# HW_RPI_10in_Rack.net
KiCad netlist of a schematic drawn in EAGLE
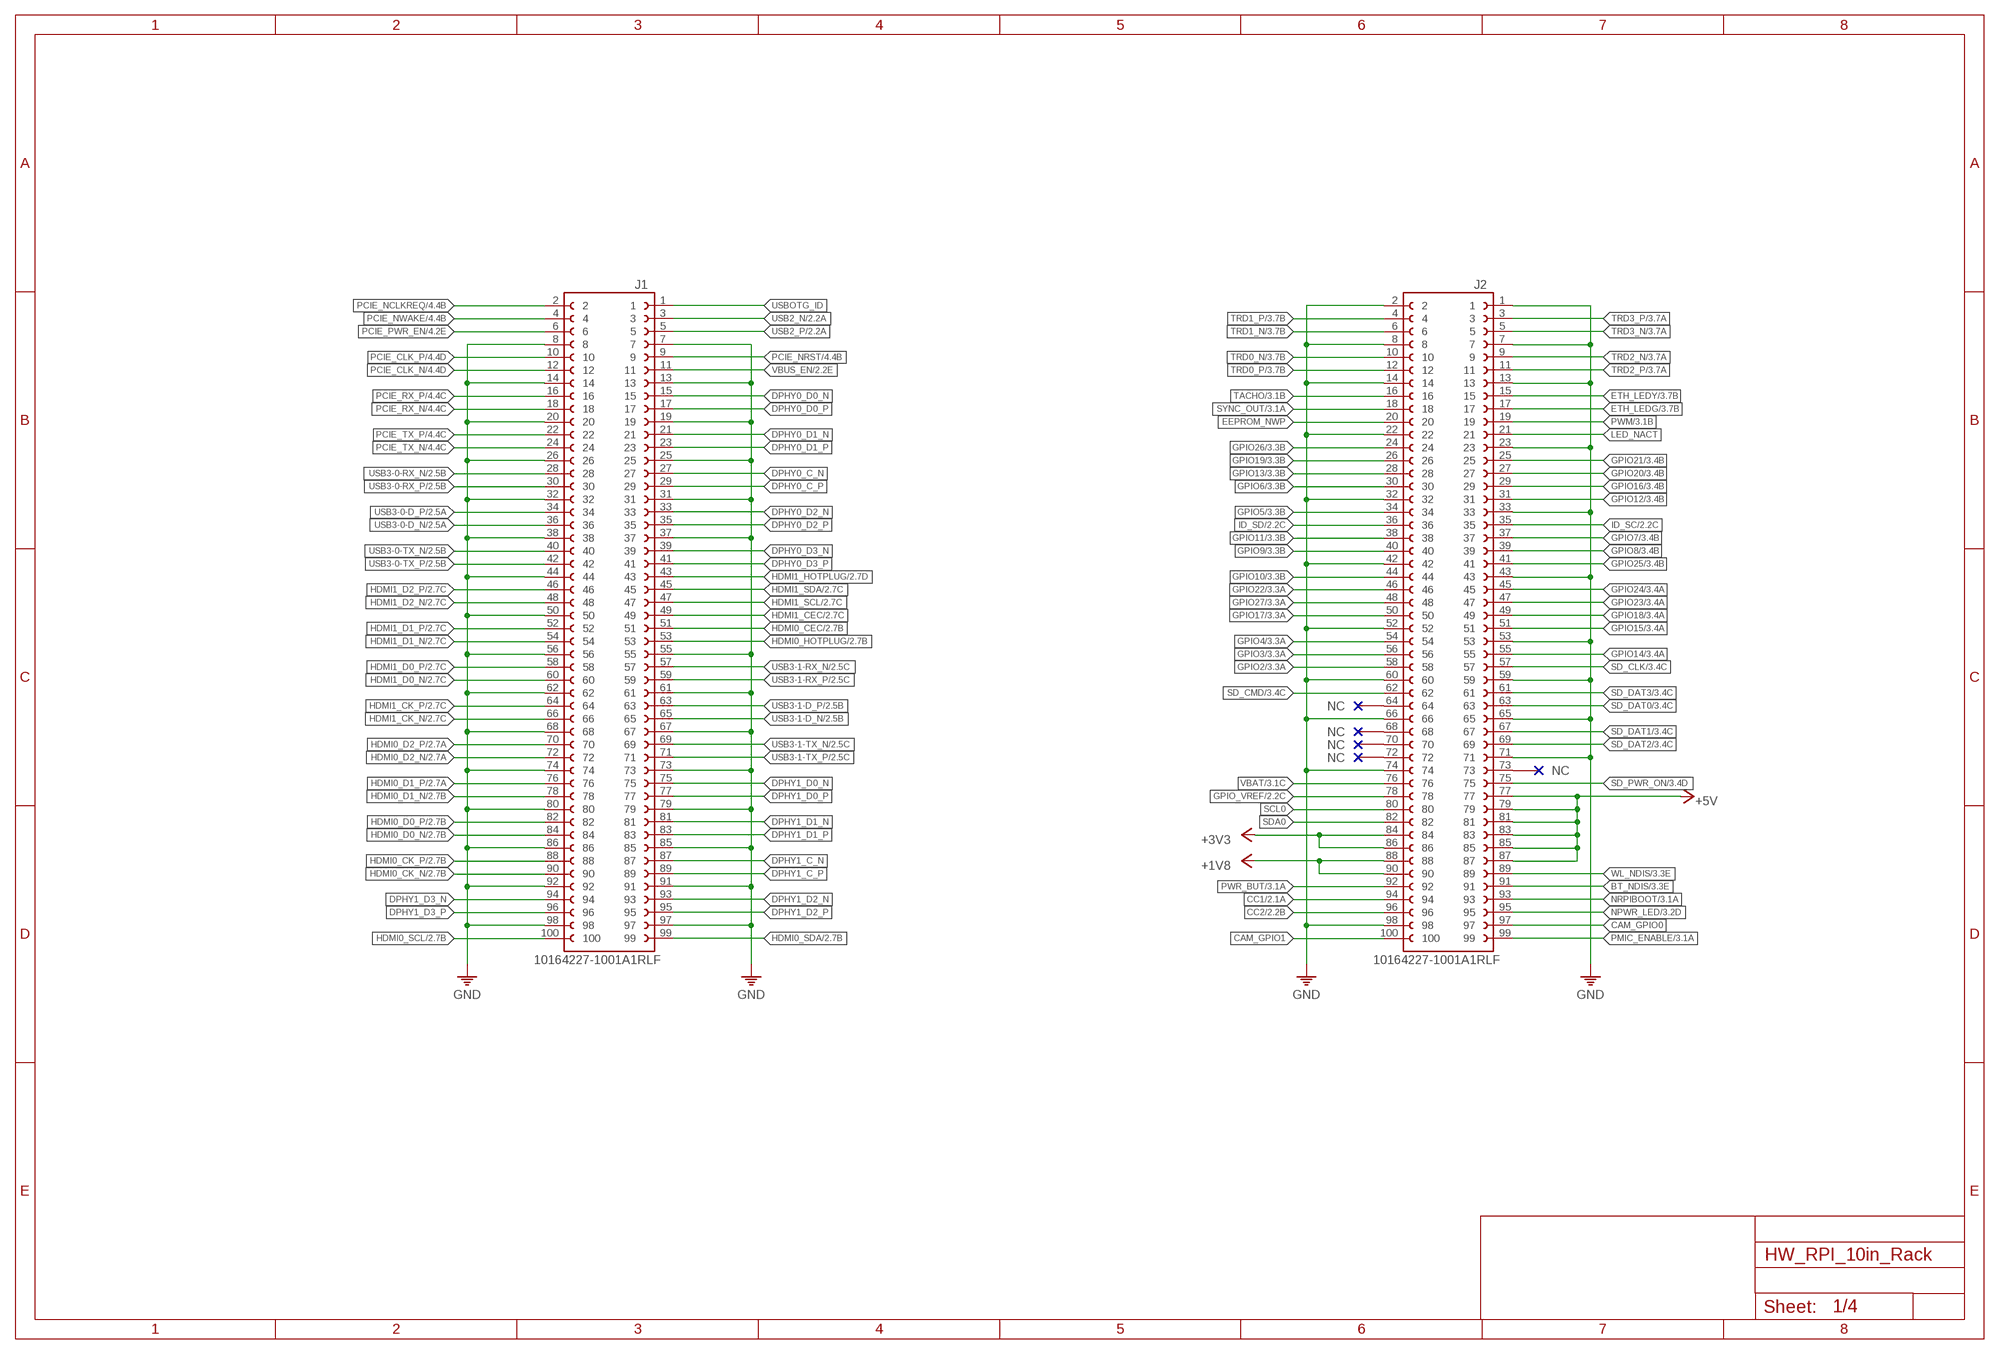
[diagram p0: schematic, sheet 1]
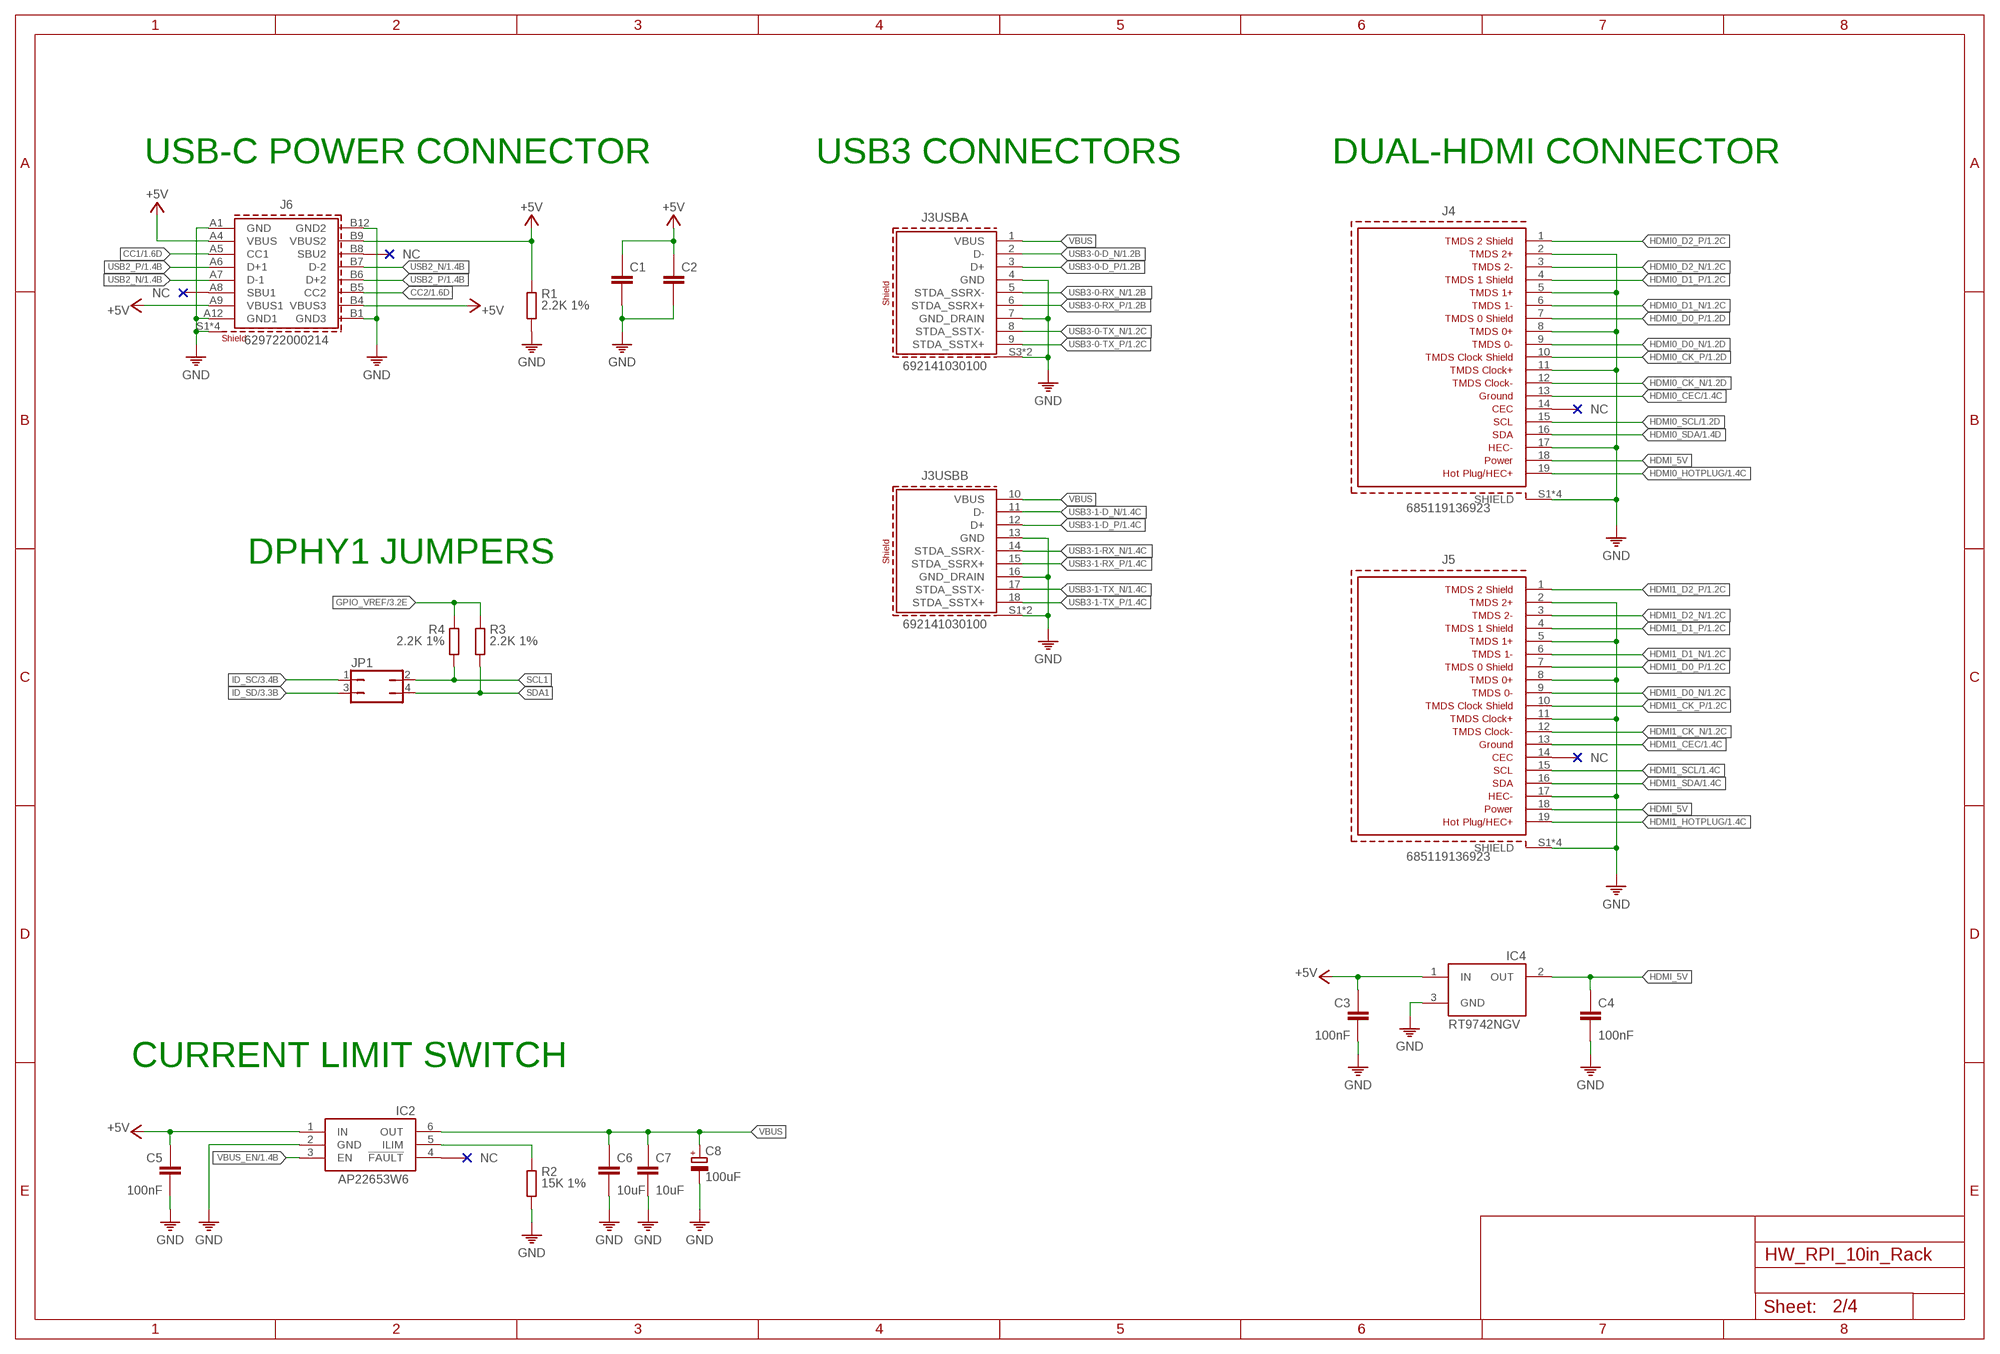
[diagram p1: schematic, sheet 2]
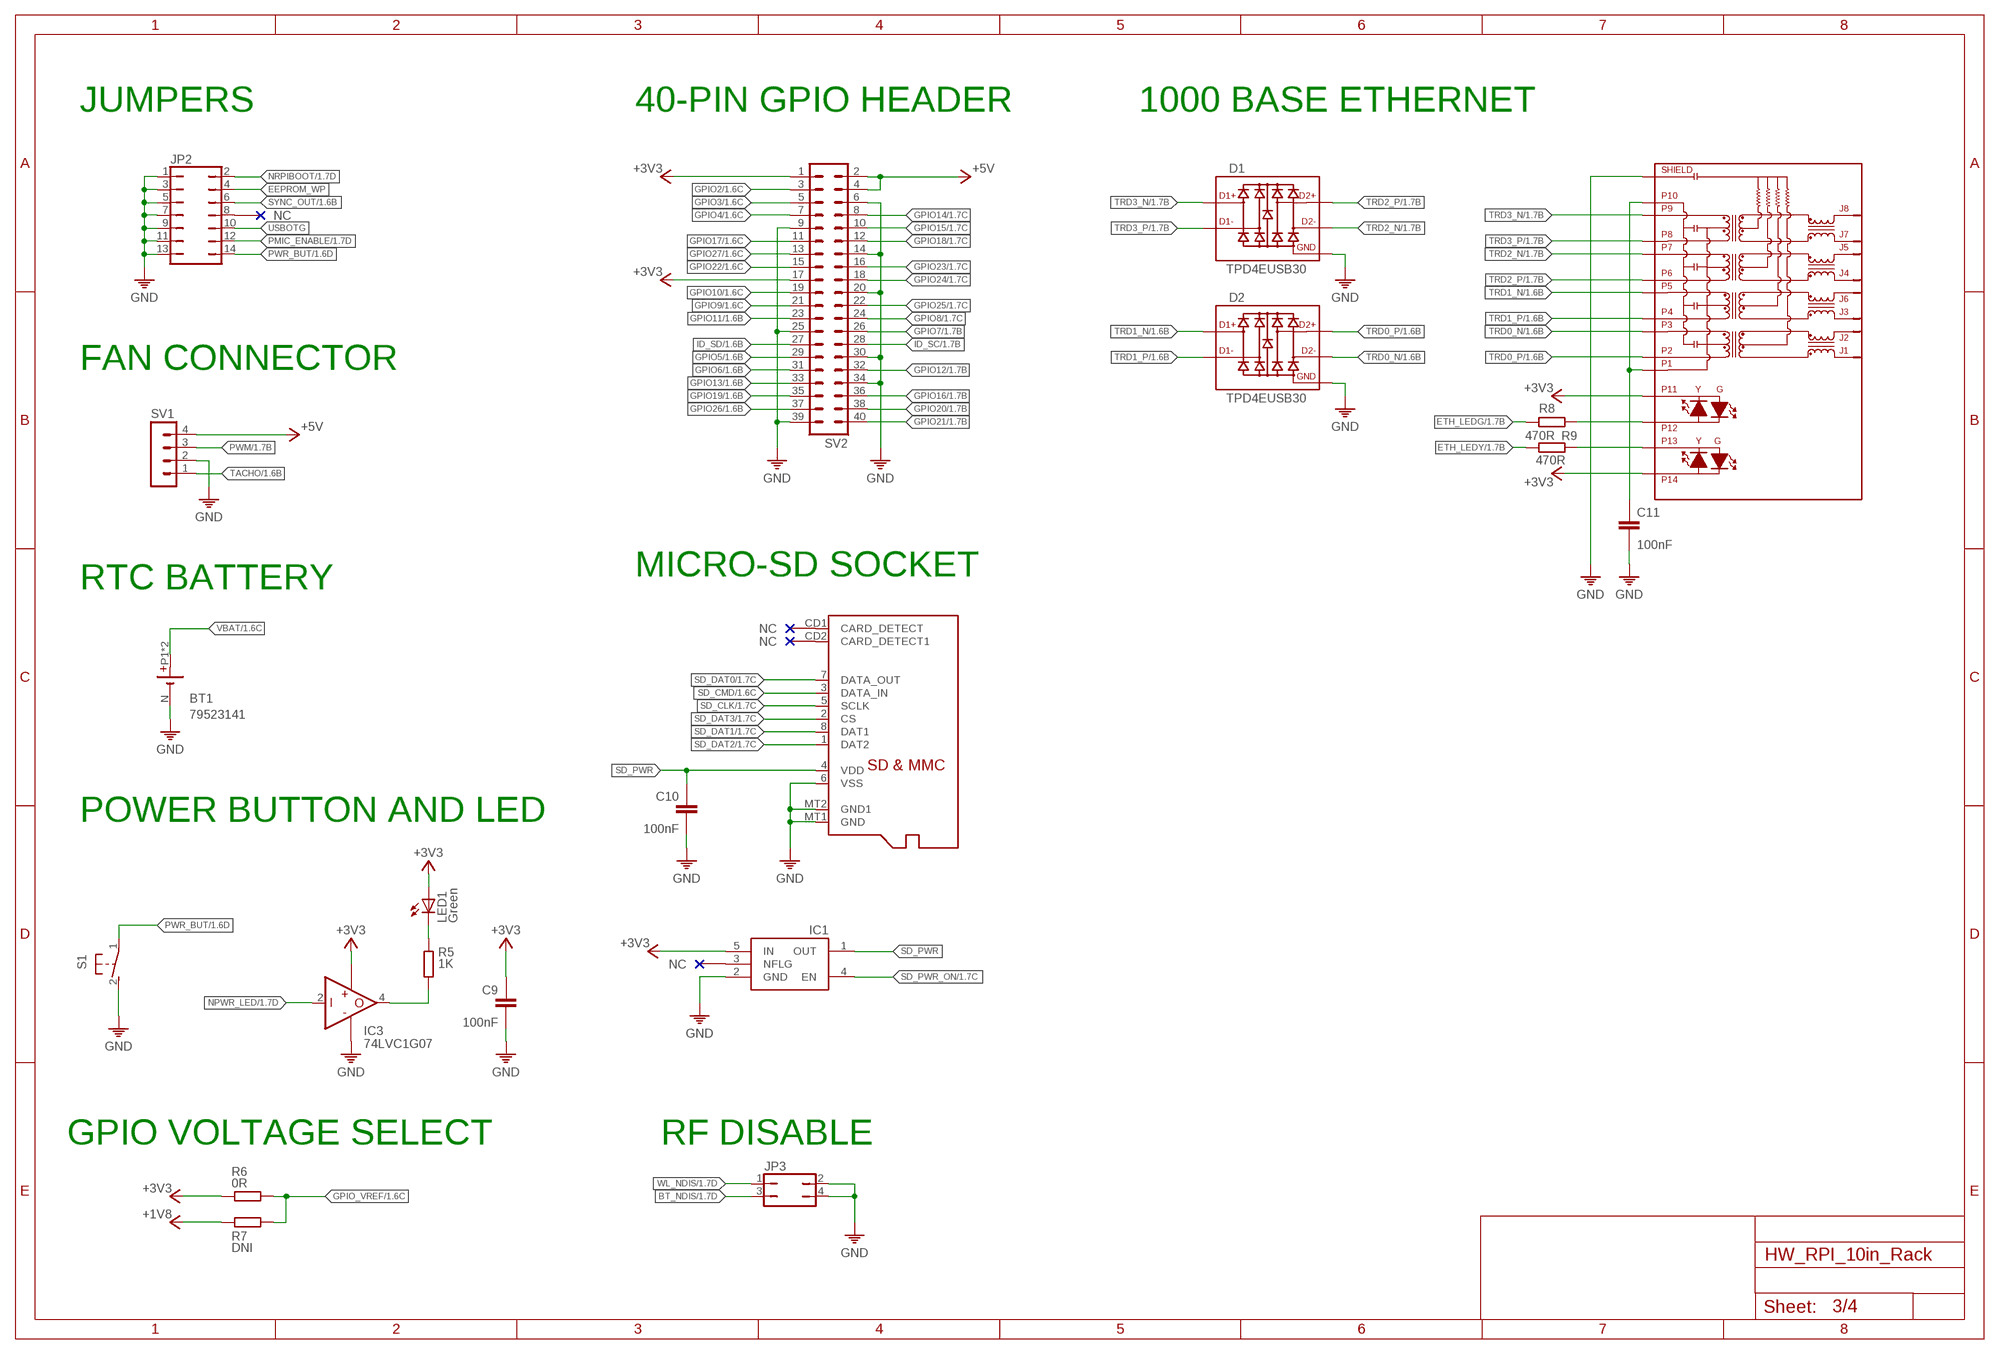
[diagram p2: schematic, sheet 3]
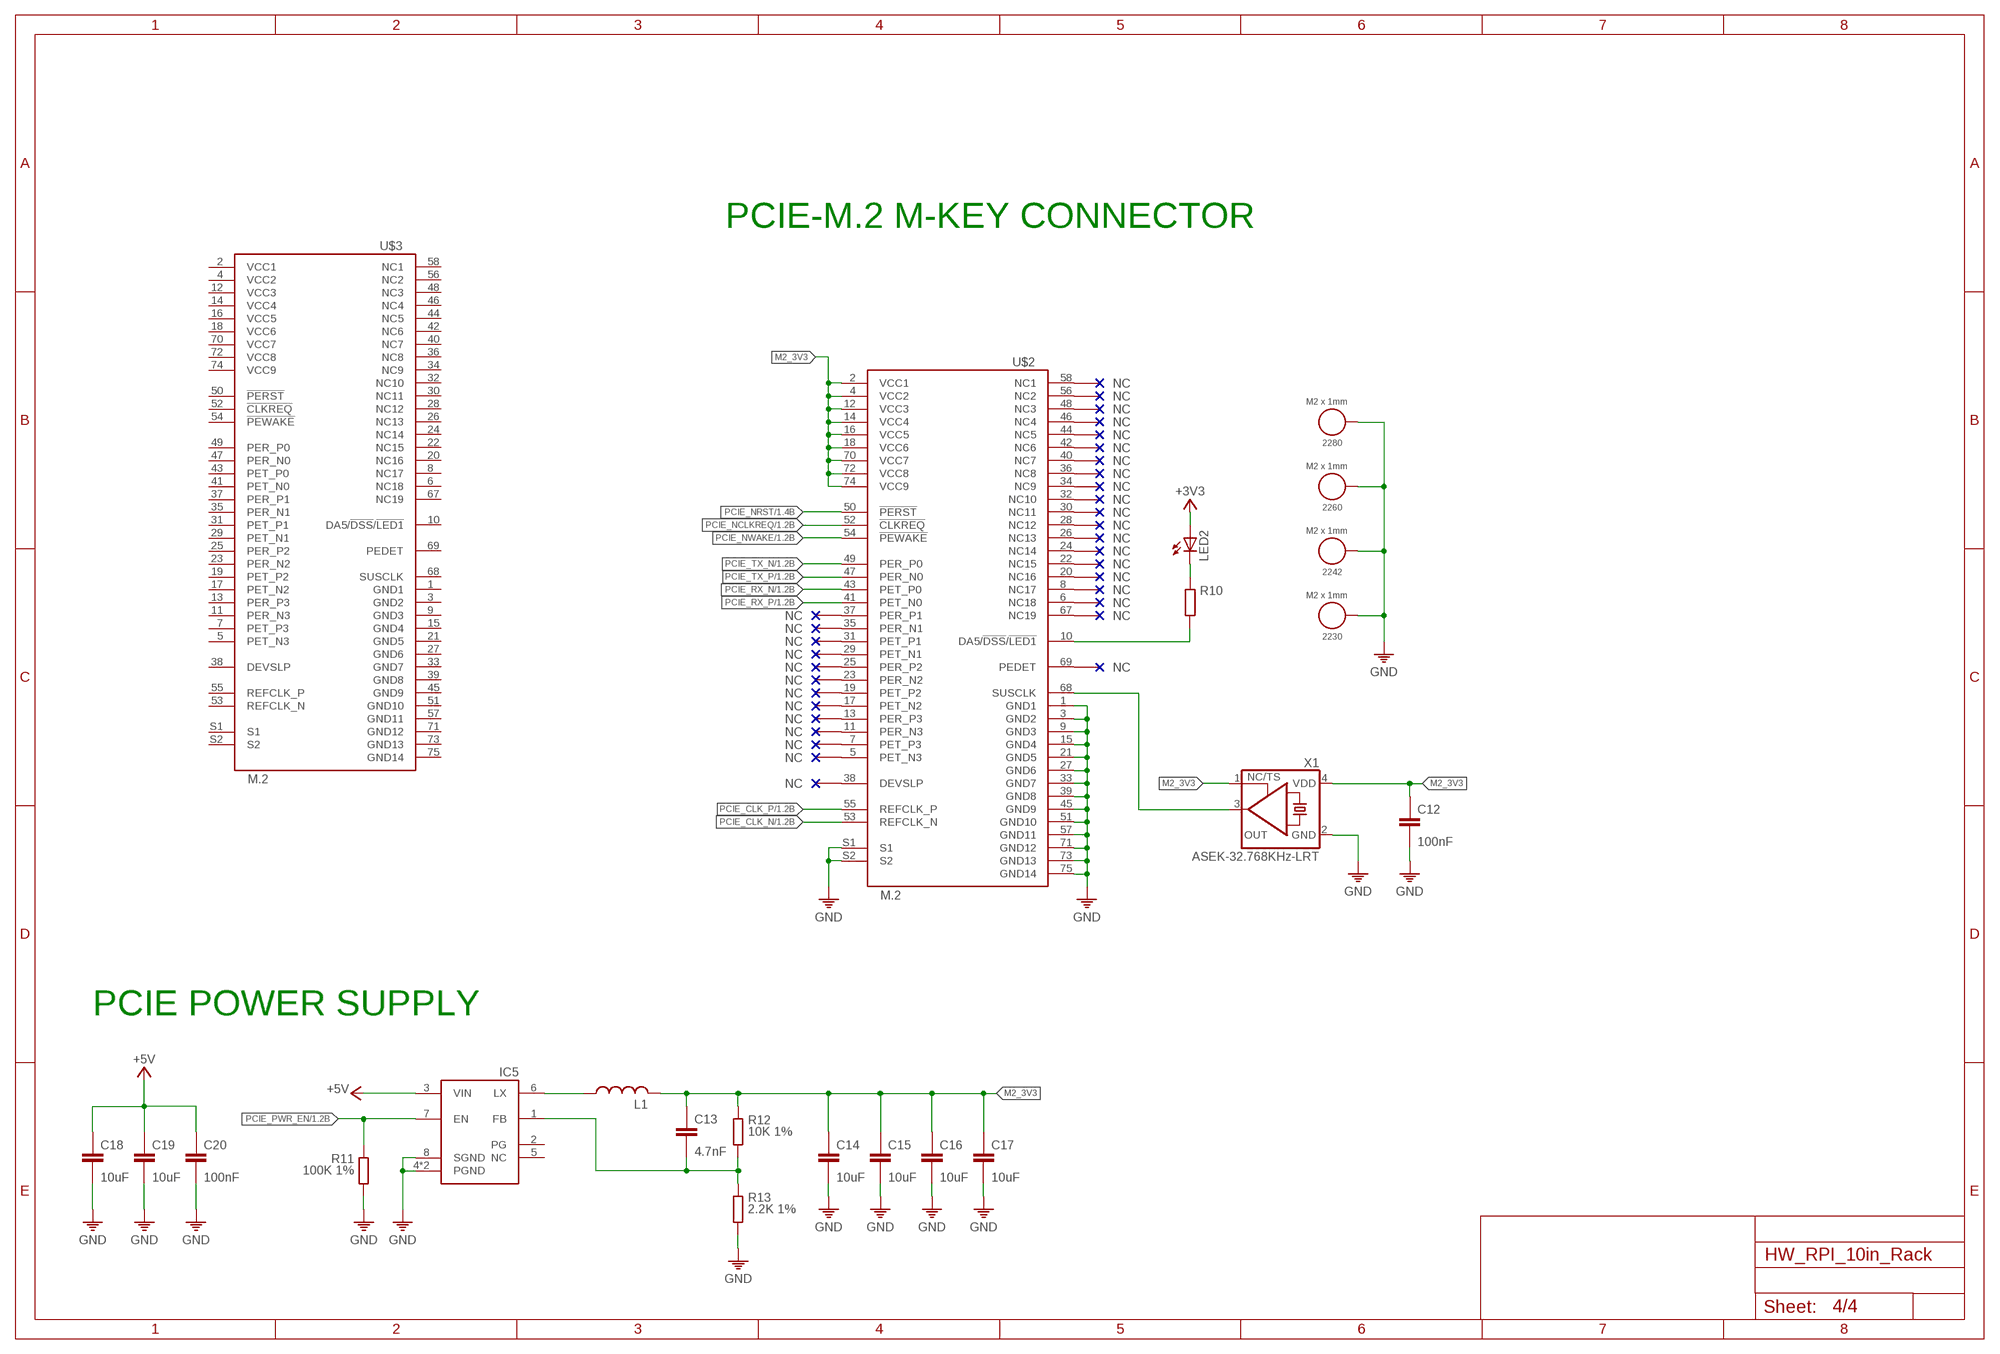
[diagram p3: schematic, sheet 4]

(export (version "E")
  (design (tool "Eeschema 10.0.6"))
  (components
    (comp (ref "J1")
      (value "10164227-1001A1RLF")
      (footprint "eagle-import:AMPHENOL_10164227-1001A1RLF")
      (fields (field (name "MANUFACTURER") "Amphenol"))
      (libsource (lib "eagle-import") (part "10164227-1001A1RLF"))
    )
    (comp (ref "J2")
      (value "10164227-1001A1RLF")
      (footprint "eagle-import:AMPHENOL_10164227-1001A1RLF")
      (fields (field (name "MANUFACTURER") "Amphenol"))
      (libsource (lib "eagle-import") (part "10164227-1001A1RLF"))
    )
    (comp (ref "C1")
      (value "C0402")
      (footprint "eagle-import:0402")
      (libsource (lib "eagle-import") (part "C0402"))
    )
    (comp (ref "C2")
      (value "C0402")
      (footprint "eagle-import:0402")
      (libsource (lib "eagle-import") (part "C0402"))
    )
    (comp (ref "C3")
      (value "100nF")
      (footprint "eagle-import:0402")
      (libsource (lib "eagle-import") (part "C0402"))
    )
    (comp (ref "C4")
      (value "100nF")
      (footprint "eagle-import:0402")
      (libsource (lib "eagle-import") (part "C0402"))
    )
    (comp (ref "C5")
      (value "100nF")
      (footprint "eagle-import:0402")
      (libsource (lib "eagle-import") (part "C0402"))
    )
    (comp (ref "C6")
      (value "10uF")
      (footprint "eagle-import:0805")
      (libsource (lib "eagle-import") (part "C0805"))
    )
    (comp (ref "C7")
      (value "10uF")
      (footprint "eagle-import:0805")
      (libsource (lib "eagle-import") (part "C0805"))
    )
    (comp (ref "C8")
      (value "100uF")
      (footprint "eagle-import:153CLV-0505")
      (libsource (lib "eagle-import") (part "CPOL-EU153CLV-0505"))
    )
    (comp (ref "IC2")
      (value "AP22653W6")
      (footprint "eagle-import:SOT23-6")
      (libsource (lib "eagle-import") (part "AP22653W6"))
    )
    (comp (ref "IC4")
      (value "RT9742NGV")
      (footprint "eagle-import:SOT23")
      (libsource (lib "eagle-import") (part "RT9742NGV"))
    )
    (comp (ref "J3")
      (value "692141030100")
      (footprint "eagle-import:692141030100")
      (libsource (lib "eagle-import") (part "692141030100"))
    )
    (comp (ref "J4")
      (value "685119136923")
      (footprint "eagle-import:685119136923")
      (libsource (lib "eagle-import") (part "685119136923"))
    )
    (comp (ref "J5")
      (value "685119136923")
      (footprint "eagle-import:685119136923")
      (libsource (lib "eagle-import") (part "685119136923"))
    )
    (comp (ref "J6")
      (value "629722000214")
      (footprint "eagle-import:629722000214")
      (libsource (lib "eagle-import") (part "629722000214"))
    )
    (comp (ref "JP1")
      (value "JP2Q")
      (footprint "eagle-import:JP2Q")
      (libsource (lib "eagle-import") (part "JP2Q"))
    )
    (comp (ref "R1")
      (value "2.2K 1%")
      (footprint "eagle-import:0402")
      (libsource (lib "eagle-import") (part "R0402"))
    )
    (comp (ref "R2")
      (value "15K 1%")
      (footprint "eagle-import:0402")
      (libsource (lib "eagle-import") (part "R0402"))
    )
    (comp (ref "R3")
      (value "2.2K 1%")
      (footprint "eagle-import:0402")
      (libsource (lib "eagle-import") (part "R0402"))
    )
    (comp (ref "R4")
      (value "2.2K 1%")
      (footprint "eagle-import:0402")
      (libsource (lib "eagle-import") (part "R0402"))
    )
    (comp (ref "2230")
      (value "M2 x 1mm")
      (footprint "eagle-import:WA-SMSI_9774010243")
      (libsource (lib "eagle-import") (part "WA-SMSI_9774XXX243_9774010243"))
    )
    (comp (ref "2242")
      (value "M2 x 1mm")
      (footprint "eagle-import:WA-SMSI_9774010243")
      (libsource (lib "eagle-import") (part "WA-SMSI_9774XXX243_9774010243"))
    )
    (comp (ref "2260")
      (value "M2 x 1mm")
      (footprint "eagle-import:WA-SMSI_9774010243")
      (libsource (lib "eagle-import") (part "WA-SMSI_9774XXX243_9774010243"))
    )
    (comp (ref "2280")
      (value "M2 x 1mm")
      (footprint "eagle-import:WA-SMSI_9774010243")
      (libsource (lib "eagle-import") (part "WA-SMSI_9774XXX243_9774010243"))
    )
    (comp (ref "C12")
      (value "100nF")
      (footprint "eagle-import:0402")
      (libsource (lib "eagle-import") (part "C0402"))
    )
    (comp (ref "C13")
      (value "4.7nF")
      (footprint "eagle-import:0402")
      (libsource (lib "eagle-import") (part "C0402"))
    )
    (comp (ref "C14")
      (value "10uF")
      (footprint "eagle-import:0805")
      (libsource (lib "eagle-import") (part "C0805"))
    )
    (comp (ref "C15")
      (value "10uF")
      (footprint "eagle-import:0805")
      (libsource (lib "eagle-import") (part "C0805"))
    )
    (comp (ref "C16")
      (value "10uF")
      (footprint "eagle-import:0805")
      (libsource (lib "eagle-import") (part "C0805"))
    )
    (comp (ref "C17")
      (value "10uF")
      (footprint "eagle-import:0805")
      (libsource (lib "eagle-import") (part "C0805"))
    )
    (comp (ref "C18")
      (value "10uF")
      (footprint "eagle-import:0805")
      (libsource (lib "eagle-import") (part "C0805"))
    )
    (comp (ref "C19")
      (value "10uF")
      (footprint "eagle-import:0805")
      (libsource (lib "eagle-import") (part "C0805"))
    )
    (comp (ref "C20")
      (value "100nF")
      (footprint "eagle-import:0402")
      (libsource (lib "eagle-import") (part "C0402"))
    )
    (comp (ref "IC5")
      (value "AP3441SHE-7B")
      (footprint "eagle-import:SON50P201X201X56-9T90X170N")
      (libsource (lib "eagle-import") (part "AP3441SHE-7B"))
    )
    (comp (ref "L1")
      (value "L-USL5038P")
      (footprint "eagle-import:L5038P")
      (libsource (lib "eagle-import") (part "L-USL5038P"))
    )
    (comp (ref "LED2")
      (value "LEDCHIPLED_0805")
      (footprint "eagle-import:CHIPLED_0805")
      (libsource (lib "eagle-import") (part "LEDCHIPLED_0805"))
    )
    (comp (ref "R10")
      (value "R0402")
      (footprint "eagle-import:0402")
      (libsource (lib "eagle-import") (part "R0402"))
    )
    (comp (ref "R11")
      (value "100K 1%")
      (footprint "eagle-import:0402")
      (libsource (lib "eagle-import") (part "R0402"))
    )
    (comp (ref "R12")
      (value "10K 1%")
      (footprint "eagle-import:0402")
      (libsource (lib "eagle-import") (part "R0402"))
    )
    (comp (ref "R13")
      (value "2.2K 1%")
      (footprint "eagle-import:0402")
      (libsource (lib "eagle-import") (part "R0402"))
    )
    (comp (ref "U$2")
      (value "M.2")
      (footprint "eagle-import:M.2")
      (libsource (lib "eagle-import") (part "M.2"))
    )
    (comp (ref "U$3")
      (value "M.2")
      (footprint "eagle-import:M.2")
      (libsource (lib "eagle-import") (part "M.2"))
    )
    (comp (ref "X1")
      (value "ASEK-32.768KHz-LRT")
      (footprint "eagle-import:3.2X2.5_KXO-V96")
      (libsource (lib "eagle-import") (part "KXO-PXO/XO-V96"))
    )
    (comp (ref "BT1")
      (value "79523141")
      (footprint "eagle-import:79523141")
      (fields
        (field (name "DIGIKEY_PART_NO") "732-12323-2-ND")
        (field (name "MANUFACTURER") "Wurth Electronics Inc.")
        (field (name "CREATED_BY") "PCBLayout.com")
      )
      (libsource (lib "eagle-import") (part "79523141"))
    )
    (comp (ref "C9")
      (value "100nF")
      (footprint "eagle-import:0402")
      (libsource (lib "eagle-import") (part "C0402"))
    )
    (comp (ref "C10")
      (value "100nF")
      (footprint "eagle-import:0402")
      (libsource (lib "eagle-import") (part "C0402"))
    )
    (comp (ref "C11")
      (value "100nF")
      (footprint "eagle-import:0402")
      (libsource (lib "eagle-import") (part "C0402"))
    )
    (comp (ref "D1")
      (value "TPD4EUSB30")
      (footprint "eagle-import:USON")
      (libsource (lib "eagle-import") (part "TPD4EUSB30"))
    )
    (comp (ref "D2")
      (value "TPD4EUSB30")
      (footprint "eagle-import:USON")
      (libsource (lib "eagle-import") (part "TPD4EUSB30"))
    )
    (comp (ref "ETH1")
      (value "MAGJACK")
      (footprint "eagle-import:RJ45")
      (libsource (lib "eagle-import") (part "MAGJACK"))
    )
    (comp (ref "IC1")
      (value "RT9742GGJ5")
      (footprint "eagle-import:SOT23-5")
      (libsource (lib "eagle-import") (part "RT9742GGJ5"))
    )
    (comp (ref "IC3")
      (value "74LVC1G07")
      (footprint "eagle-import:SOT23-5")
      (libsource (lib "eagle-import") (part "74LVC1G07"))
    )
    (comp (ref "JP2")
      (value "JP7Q")
      (footprint "eagle-import:JP7Q")
      (libsource (lib "eagle-import") (part "JP7Q"))
    )
    (comp (ref "JP3")
      (value "JP2Q")
      (footprint "eagle-import:JP2Q")
      (libsource (lib "eagle-import") (part "JP2Q"))
    )
    (comp (ref "LED1")
      (value "Green")
      (footprint "eagle-import:CHIPLED_0805")
      (libsource (lib "eagle-import") (part "LEDCHIPLED_0805"))
    )
    (comp (ref "R5")
      (value "1K")
      (footprint "eagle-import:0402")
      (libsource (lib "eagle-import") (part "R0402"))
    )
    (comp (ref "R6")
      (value "0R")
      (footprint "eagle-import:0402")
      (libsource (lib "eagle-import") (part "R0402"))
    )
    (comp (ref "R7")
      (value "DNI")
      (footprint "eagle-import:0402")
      (libsource (lib "eagle-import") (part "R0402"))
    )
    (comp (ref "R8")
      (value "470R")
      (footprint "eagle-import:0402")
      (libsource (lib "eagle-import") (part "R0402"))
    )
    (comp (ref "R9")
      (value "470R")
      (footprint "eagle-import:0402")
      (libsource (lib "eagle-import") (part "R0402"))
    )
    (comp (ref "S1")
      (value "31-XX")
      (footprint "eagle-import:B3F-31XX")
      (libsource (lib "eagle-import") (part "31-XX"))
    )
    (comp (ref "SV1")
      (value "MA04-1")
      (footprint "eagle-import:MA04-1")
      (libsource (lib "eagle-import") (part "MA04-1"))
    )
    (comp (ref "SV2")
      (value "MA20-2")
      (footprint "eagle-import:MA20-2")
      (libsource (lib "eagle-import") (part "MA20-2"))
    )
    (comp (ref "U$1")
      (value "MICROSD")
      (footprint "eagle-import:MICROSD")
      (libsource (lib "eagle-import") (part "MICROSD"))
    )
  )
  (nets
    (net (code "1") (name "+1V8") (class "Default")
      (node (ref "J2") (pin "88") (pinfunction "88_88") (pintype "passive"))
      (node (ref "J2") (pin "90") (pinfunction "90_90") (pintype "passive"))
      (node (ref "R7") (pin "1") (pinfunction "1_1") (pintype "passive"))
    )
    (net (code "2") (name "+3V3") (class "Default")
      (node (ref "C9") (pin "1") (pinfunction "1_1") (pintype "passive"))
      (node (ref "ETH1") (pin "P11") (pinfunction "P11_P11") (pintype "bidirectional"))
      (node (ref "ETH1") (pin "P14") (pinfunction "P14_P14") (pintype "bidirectional"))
      (node (ref "IC1") (pin "5") (pinfunction "IN_5") (pintype "power_in"))
      (node (ref "IC3") (pin "5") (pinfunction "VCC_5") (pintype "bidirectional"))
      (node (ref "J2") (pin "84") (pinfunction "84_84") (pintype "passive"))
      (node (ref "J2") (pin "86") (pinfunction "86_86") (pintype "passive"))
      (node (ref "LED1") (pin "A") (pinfunction "A_A") (pintype "passive"))
      (node (ref "LED2") (pin "A") (pinfunction "A_A") (pintype "passive"))
      (node (ref "R6") (pin "1") (pinfunction "1_1") (pintype "passive"))
      (node (ref "SV2") (pin "1") (pinfunction "1_1") (pintype "passive"))
      (node (ref "SV2") (pin "17") (pinfunction "17_17") (pintype "passive"))
    )
    (net (code "3") (name "+5V") (class "Default")
      (node (ref "C1") (pin "1") (pinfunction "1_1") (pintype "passive"))
      (node (ref "C18") (pin "1") (pinfunction "1_1") (pintype "passive"))
      (node (ref "C19") (pin "1") (pinfunction "1_1") (pintype "passive"))
      (node (ref "C2") (pin "1") (pinfunction "1_1") (pintype "passive"))
      (node (ref "C20") (pin "1") (pinfunction "1_1") (pintype "passive"))
      (node (ref "C3") (pin "1") (pinfunction "1_1") (pintype "passive"))
      (node (ref "C5") (pin "1") (pinfunction "1_1") (pintype "passive"))
      (node (ref "IC2") (pin "1") (pinfunction "IN_1") (pintype "bidirectional"))
      (node (ref "IC4") (pin "1") (pinfunction "IN_1") (pintype "power_in"))
      (node (ref "IC5") (pin "3") (pinfunction "VIN_3") (pintype "power_in"))
      (node (ref "J2") (pin "77") (pinfunction "77_77") (pintype "passive"))
      (node (ref "J2") (pin "79") (pinfunction "79_79") (pintype "passive"))
      (node (ref "J2") (pin "81") (pinfunction "81_81") (pintype "passive"))
      (node (ref "J2") (pin "83") (pinfunction "83_83") (pintype "passive"))
      (node (ref "J2") (pin "85") (pinfunction "85_85") (pintype "passive"))
      (node (ref "J2") (pin "87") (pinfunction "87_87") (pintype "passive"))
      (node (ref "J6") (pin "A4") (pinfunction "VBUS_A4") (pintype "passive"))
      (node (ref "J6") (pin "A9") (pinfunction "VBUS1_A9") (pintype "passive"))
      (node (ref "J6") (pin "B4") (pinfunction "VBUS3_B4") (pintype "passive"))
      (node (ref "J6") (pin "B9") (pinfunction "VBUS2_B9") (pintype "passive"))
      (node (ref "R1") (pin "1") (pinfunction "1_1") (pintype "passive"))
      (node (ref "SV1") (pin "4") (pinfunction "4_4") (pintype "passive"))
      (node (ref "SV2") (pin "2") (pinfunction "2_2") (pintype "passive"))
      (node (ref "SV2") (pin "4") (pinfunction "4_4") (pintype "passive"))
    )
    (net (code "4") (name "BT_NDIS") (class "Default")
      (node (ref "J2") (pin "91") (pinfunction "91_91") (pintype "passive"))
      (node (ref "JP3") (pin "3") (pinfunction "3_3") (pintype "passive"))
    )
    (net (code "5") (name "CAM_GPIO0") (class "Default")
      (node (ref "J2") (pin "97") (pinfunction "97_97") (pintype "passive"))
    )
    (net (code "6") (name "CAM_GPIO1") (class "Default")
      (node (ref "J2") (pin "100") (pinfunction "100_100") (pintype "passive"))
    )
    (net (code "7") (name "CC1") (class "Default")
      (node (ref "J2") (pin "94") (pinfunction "94_94") (pintype "passive"))
      (node (ref "J6") (pin "A5") (pinfunction "CC1_A5") (pintype "passive"))
    )
    (net (code "8") (name "CC2") (class "Default")
      (node (ref "J2") (pin "96") (pinfunction "96_96") (pintype "passive"))
      (node (ref "J6") (pin "B5") (pinfunction "CC2_B5") (pintype "passive"))
    )
    (net (code "9") (name "DPHY0_C_N") (class "Default")
      (node (ref "J1") (pin "27") (pinfunction "27_27") (pintype "passive"))
    )
    (net (code "10") (name "DPHY0_C_P") (class "Default")
      (node (ref "J1") (pin "29") (pinfunction "29_29") (pintype "passive"))
    )
    (net (code "11") (name "DPHY0_D0_N") (class "Default")
      (node (ref "J1") (pin "15") (pinfunction "15_15") (pintype "passive"))
    )
    (net (code "12") (name "DPHY0_D0_P") (class "Default")
      (node (ref "J1") (pin "17") (pinfunction "17_17") (pintype "passive"))
    )
    (net (code "13") (name "DPHY0_D1_N") (class "Default")
      (node (ref "J1") (pin "21") (pinfunction "21_21") (pintype "passive"))
    )
    (net (code "14") (name "DPHY0_D1_P") (class "Default")
      (node (ref "J1") (pin "23") (pinfunction "23_23") (pintype "passive"))
    )
    (net (code "15") (name "DPHY0_D2_N") (class "Default")
      (node (ref "J1") (pin "33") (pinfunction "33_33") (pintype "passive"))
    )
    (net (code "16") (name "DPHY0_D2_P") (class "Default")
      (node (ref "J1") (pin "35") (pinfunction "35_35") (pintype "passive"))
    )
    (net (code "17") (name "DPHY0_D3_N") (class "Default")
      (node (ref "J1") (pin "39") (pinfunction "39_39") (pintype "passive"))
    )
    (net (code "18") (name "DPHY0_D3_P") (class "Default")
      (node (ref "J1") (pin "41") (pinfunction "41_41") (pintype "passive"))
    )
    (net (code "19") (name "DPHY1_C_N") (class "Default")
      (node (ref "J1") (pin "87") (pinfunction "87_87") (pintype "passive"))
    )
    (net (code "20") (name "DPHY1_C_P") (class "Default")
      (node (ref "J1") (pin "89") (pinfunction "89_89") (pintype "passive"))
    )
    (net (code "21") (name "DPHY1_D0_N") (class "Default")
      (node (ref "J1") (pin "75") (pinfunction "75_75") (pintype "passive"))
    )
    (net (code "22") (name "DPHY1_D0_P") (class "Default")
      (node (ref "J1") (pin "77") (pinfunction "77_77") (pintype "passive"))
    )
    (net (code "23") (name "DPHY1_D1_N") (class "Default")
      (node (ref "J1") (pin "81") (pinfunction "81_81") (pintype "passive"))
    )
    (net (code "24") (name "DPHY1_D1_P") (class "Default")
      (node (ref "J1") (pin "83") (pinfunction "83_83") (pintype "passive"))
    )
    (net (code "25") (name "DPHY1_D2_N") (class "Default")
      (node (ref "J1") (pin "93") (pinfunction "93_93") (pintype "passive"))
    )
    (net (code "26") (name "DPHY1_D2_P") (class "Default")
      (node (ref "J1") (pin "95") (pinfunction "95_95") (pintype "passive"))
    )
    (net (code "27") (name "DPHY1_D3_N") (class "Default")
      (node (ref "J1") (pin "94") (pinfunction "94_94") (pintype "passive"))
    )
    (net (code "28") (name "DPHY1_D3_P") (class "Default")
      (node (ref "J1") (pin "96") (pinfunction "96_96") (pintype "passive"))
    )
    (net (code "29") (name "EEPROM_NWP") (class "Default")
      (node (ref "J2") (pin "20") (pinfunction "20_20") (pintype "passive"))
    )
    (net (code "30") (name "EEPROM_WP") (class "Default")
      (node (ref "JP2") (pin "4") (pinfunction "4_4") (pintype "passive"))
    )
    (net (code "31") (name "ETH_LEDG") (class "Default")
      (node (ref "J2") (pin "17") (pinfunction "17_17") (pintype "passive"))
      (node (ref "R8") (pin "1") (pinfunction "1_1") (pintype "passive"))
    )
    (net (code "32") (name "ETH_LEDY") (class "Default")
      (node (ref "J2") (pin "15") (pinfunction "15_15") (pintype "passive"))
      (node (ref "R9") (pin "2") (pinfunction "2_2") (pintype "passive"))
    )
    (net (code "33") (name "GND") (class "Default")
      (node (ref "2230") (pin "1") (pinfunction "1_1") (pintype "passive"))
      (node (ref "2242") (pin "1") (pinfunction "1_1") (pintype "passive"))
      (node (ref "2260") (pin "1") (pinfunction "1_1") (pintype "passive"))
      (node (ref "2280") (pin "1") (pinfunction "1_1") (pintype "passive"))
      (node (ref "BT1") (pin "N") (pinfunction "-_N") (pintype "passive"))
      (node (ref "C1") (pin "2") (pinfunction "2_2") (pintype "passive"))
      (node (ref "C10") (pin "2") (pinfunction "2_2") (pintype "passive"))
      (node (ref "C11") (pin "2") (pinfunction "2_2") (pintype "passive"))
      (node (ref "C12") (pin "2") (pinfunction "2_2") (pintype "passive"))
      (node (ref "C14") (pin "2") (pinfunction "2_2") (pintype "passive"))
      (node (ref "C15") (pin "2") (pinfunction "2_2") (pintype "passive"))
      (node (ref "C16") (pin "2") (pinfunction "2_2") (pintype "passive"))
      (node (ref "C17") (pin "2") (pinfunction "2_2") (pintype "passive"))
      (node (ref "C18") (pin "2") (pinfunction "2_2") (pintype "passive"))
      (node (ref "C19") (pin "2") (pinfunction "2_2") (pintype "passive"))
      (node (ref "C2") (pin "2") (pinfunction "2_2") (pintype "passive"))
      (node (ref "C20") (pin "2") (pinfunction "2_2") (pintype "passive"))
      (node (ref "C3") (pin "2") (pinfunction "2_2") (pintype "passive"))
      (node (ref "C4") (pin "2") (pinfunction "2_2") (pintype "passive"))
      (node (ref "C5") (pin "2") (pinfunction "2_2") (pintype "passive"))
      (node (ref "C6") (pin "2") (pinfunction "2_2") (pintype "passive"))
      (node (ref "C7") (pin "2") (pinfunction "2_2") (pintype "passive"))
      (node (ref "C8") (pin "-") (pinfunction "-_-") (pintype "passive"))
      (node (ref "C9") (pin "2") (pinfunction "2_2") (pintype "passive"))
      (node (ref "D1") (pin "3") (pinfunction "GND_3") (pintype "bidirectional"))
      (node (ref "D1") (pin "8") (pinfunction "GND_8") (pintype "bidirectional"))
      (node (ref "D2") (pin "3") (pinfunction "GND_3") (pintype "bidirectional"))
      (node (ref "D2") (pin "8") (pinfunction "GND_8") (pintype "bidirectional"))
      (node (ref "ETH1") (pin "MH3") (pinfunction "SHIELD_MH3") (pintype "bidirectional"))
      (node (ref "ETH1") (pin "MH4") (pinfunction "SHIELD_MH4") (pintype "bidirectional"))
      (node (ref "IC1") (pin "2") (pinfunction "GND_2") (pintype "power_in"))
      (node (ref "IC2") (pin "2") (pinfunction "GND_2") (pintype "bidirectional"))
      (node (ref "IC3") (pin "3") (pinfunction "GND_3") (pintype "bidirectional"))
      (node (ref "IC4") (pin "3") (pinfunction "GND_3") (pintype "power_in"))
      (node (ref "IC5") (pin "4") (pinfunction "PGND_4") (pintype "power_in"))
      (node (ref "IC5") (pin "8") (pinfunction "SGND_8") (pintype "power_in"))
      (node (ref "IC5") (pin "9") (pinfunction "PGND_9") (pintype "power_in"))
      (node (ref "J1") (pin "13") (pinfunction "13_13") (pintype "passive"))
      (node (ref "J1") (pin "14") (pinfunction "14_14") (pintype "passive"))
      (node (ref "J1") (pin "19") (pinfunction "19_19") (pintype "passive"))
      (node (ref "J1") (pin "20") (pinfunction "20_20") (pintype "passive"))
      (node (ref "J1") (pin "25") (pinfunction "25_25") (pintype "passive"))
      (node (ref "J1") (pin "26") (pinfunction "26_26") (pintype "passive"))
      (node (ref "J1") (pin "31") (pinfunction "31_31") (pintype "passive"))
      (node (ref "J1") (pin "32") (pinfunction "32_32") (pintype "passive"))
      (node (ref "J1") (pin "37") (pinfunction "37_37") (pintype "passive"))
      (node (ref "J1") (pin "38") (pinfunction "38_38") (pintype "passive"))
      (node (ref "J1") (pin "44") (pinfunction "44_44") (pintype "passive"))
      (node (ref "J1") (pin "50") (pinfunction "50_50") (pintype "passive"))
      (node (ref "J1") (pin "55") (pinfunction "55_55") (pintype "passive"))
      (node (ref "J1") (pin "56") (pinfunction "56_56") (pintype "passive"))
      (node (ref "J1") (pin "61") (pinfunction "61_61") (pintype "passive"))
      (node (ref "J1") (pin "62") (pinfunction "62_62") (pintype "passive"))
      (node (ref "J1") (pin "67") (pinfunction "67_67") (pintype "passive"))
      (node (ref "J1") (pin "68") (pinfunction "68_68") (pintype "passive"))
      (node (ref "J1") (pin "7") (pinfunction "7_7") (pintype "passive"))
      (node (ref "J1") (pin "73") (pinfunction "73_73") (pintype "passive"))
      (node (ref "J1") (pin "74") (pinfunction "74_74") (pintype "passive"))
      (node (ref "J1") (pin "79") (pinfunction "79_79") (pintype "passive"))
      (node (ref "J1") (pin "8") (pinfunction "8_8") (pintype "passive"))
      (node (ref "J1") (pin "80") (pinfunction "80_80") (pintype "passive"))
      (node (ref "J1") (pin "85") (pinfunction "85_85") (pintype "passive"))
      (node (ref "J1") (pin "86") (pinfunction "86_86") (pintype "passive"))
      (node (ref "J1") (pin "91") (pinfunction "91_91") (pintype "passive"))
      (node (ref "J1") (pin "92") (pinfunction "92_92") (pintype "passive"))
      (node (ref "J1") (pin "97") (pinfunction "97_97") (pintype "passive"))
      (node (ref "J1") (pin "98") (pinfunction "98_98") (pintype "passive"))
      (node (ref "J2") (pin "1") (pinfunction "1_1") (pintype "passive"))
      (node (ref "J2") (pin "13") (pinfunction "13_13") (pintype "passive"))
      (node (ref "J2") (pin "14") (pinfunction "14_14") (pintype "passive"))
      (node (ref "J2") (pin "2") (pinfunction "2_2") (pintype "passive"))
      (node (ref "J2") (pin "22") (pinfunction "22_22") (pintype "passive"))
      (node (ref "J2") (pin "23") (pinfunction "23_23") (pintype "passive"))
      (node (ref "J2") (pin "32") (pinfunction "32_32") (pintype "passive"))
      (node (ref "J2") (pin "33") (pinfunction "33_33") (pintype "passive"))
      (node (ref "J2") (pin "42") (pinfunction "42_42") (pintype "passive"))
      (node (ref "J2") (pin "43") (pinfunction "43_43") (pintype "passive"))
      (node (ref "J2") (pin "52") (pinfunction "52_52") (pintype "passive"))
      (node (ref "J2") (pin "53") (pinfunction "53_53") (pintype "passive"))
      (node (ref "J2") (pin "59") (pinfunction "59_59") (pintype "passive"))
      (node (ref "J2") (pin "60") (pinfunction "60_60") (pintype "passive"))
      (node (ref "J2") (pin "65") (pinfunction "65_65") (pintype "passive"))
      (node (ref "J2") (pin "66") (pinfunction "66_66") (pintype "passive"))
      (node (ref "J2") (pin "7") (pinfunction "7_7") (pintype "passive"))
      (node (ref "J2") (pin "71") (pinfunction "71_71") (pintype "passive"))
      (node (ref "J2") (pin "74") (pinfunction "74_74") (pintype "passive"))
      (node (ref "J2") (pin "8") (pinfunction "8_8") (pintype "passive"))
      (node (ref "J2") (pin "98") (pinfunction "98_98") (pintype "passive"))
      (node (ref "J3") (pin "13") (pinfunction "GND_13") (pintype "passive"))
      (node (ref "J3") (pin "16") (pinfunction "GND_DRAIN_16") (pintype "passive"))
      (node (ref "J3") (pin "4") (pinfunction "GND_4") (pintype "passive"))
      (node (ref "J3") (pin "7") (pinfunction "GND_DRAIN_7") (pintype "passive"))
      (node (ref "J3") (pin "S1") (pinfunction "SHIELD_S1") (pintype "passive"))
      (node (ref "J3") (pin "S2") (pinfunction "SHIELD_S2") (pintype "passive"))
      (node (ref "J3") (pin "S3") (pinfunction "SHIELD_S3") (pintype "passive"))
      (node (ref "J3") (pin "S4") (pinfunction "SHIELD_S4") (pintype "passive"))
      (node (ref "J4") (pin "11") (pinfunction "TMDSCLOCK+_11") (pintype "passive"))
      (node (ref "J4") (pin "17") (pinfunction "UTILITY/HEAC+_17") (pintype "passive"))
      (node (ref "J4") (pin "2") (pinfunction "TMDS2+_2") (pintype "passive"))
      (node (ref "J4") (pin "5") (pinfunction "TMDSDATA1+_5") (pintype "passive"))
      (node (ref "J4") (pin "8") (pinfunction "TMDS0+_8") (pintype "passive"))
      (node (ref "J4") (pin "S1") (pinfunction "SHIELD_S1") (pintype "passive"))
      (node (ref "J4") (pin "S2") (pinfunction "SHIELD_S2") (pintype "passive"))
      (node (ref "J4") (pin "S3") (pinfunction "SHIELD_S3") (pintype "passive"))
      (node (ref "J4") (pin "S4") (pinfunction "SHIELD_S4") (pintype "passive"))
      (node (ref "J5") (pin "11") (pinfunction "TMDSCLOCK+_11") (pintype "passive"))
      (node (ref "J5") (pin "17") (pinfunction "UTILITY/HEAC+_17") (pintype "passive"))
      (node (ref "J5") (pin "2") (pinfunction "TMDS2+_2") (pintype "passive"))
      (node (ref "J5") (pin "5") (pinfunction "TMDSDATA1+_5") (pintype "passive"))
      (node (ref "J5") (pin "8") (pinfunction "TMDS0+_8") (pintype "passive"))
      (node (ref "J5") (pin "S1") (pinfunction "SHIELD_S1") (pintype "passive"))
      (node (ref "J5") (pin "S2") (pinfunction "SHIELD_S2") (pintype "passive"))
      (node (ref "J5") (pin "S3") (pinfunction "SHIELD_S3") (pintype "passive"))
      (node (ref "J5") (pin "S4") (pinfunction "SHIELD_S4") (pintype "passive"))
      (node (ref "J6") (pin "A1") (pinfunction "GND_A1") (pintype "passive"))
      (node (ref "J6") (pin "A12") (pinfunction "GND1_A12") (pintype "passive"))
      (node (ref "J6") (pin "B1") (pinfunction "GND3_B1") (pintype "passive"))
      (node (ref "J6") (pin "B12") (pinfunction "GND2_B12") (pintype "passive"))
      (node (ref "J6") (pin "S1") (pinfunction "SHIELD_S1") (pintype "passive"))
      (node (ref "J6") (pin "S2") (pinfunction "SHIELD_S2") (pintype "passive"))
      (node (ref "J6") (pin "S3") (pinfunction "SHIELD_S3") (pintype "passive"))
      (node (ref "J6") (pin "S4") (pinfunction "SHIELD_S4") (pintype "passive"))
      (node (ref "JP2") (pin "1") (pinfunction "1_1") (pintype "passive"))
      (node (ref "JP2") (pin "11") (pinfunction "11_11") (pintype "passive"))
      (node (ref "JP2") (pin "13") (pinfunction "13_13") (pintype "passive"))
      (node (ref "JP2") (pin "3") (pinfunction "3_3") (pintype "passive"))
      (node (ref "JP2") (pin "5") (pinfunction "5_5") (pintype "passive"))
      (node (ref "JP2") (pin "7") (pinfunction "7_7") (pintype "passive"))
      (node (ref "JP2") (pin "9") (pinfunction "9_9") (pintype "passive"))
      (node (ref "JP3") (pin "2") (pinfunction "2_2") (pintype "passive"))
      (node (ref "JP3") (pin "4") (pinfunction "4_4") (pintype "passive"))
      (node (ref "R1") (pin "2") (pinfunction "2_2") (pintype "passive"))
      (node (ref "R11") (pin "2") (pinfunction "2_2") (pintype "passive"))
      (node (ref "R13") (pin "2") (pinfunction "2_2") (pintype "passive"))
      (node (ref "R2") (pin "2") (pinfunction "2_2") (pintype "passive"))
      (node (ref "S1") (pin "2") (pinfunction "S_2") (pintype "passive"))
      (node (ref "SV1") (pin "2") (pinfunction "2_2") (pintype "passive"))
      (node (ref "SV2") (pin "14") (pinfunction "14_14") (pintype "passive"))
      (node (ref "SV2") (pin "20") (pinfunction "20_20") (pintype "passive"))
      (node (ref "SV2") (pin "25") (pinfunction "25_25") (pintype "passive"))
      (node (ref "SV2") (pin "30") (pinfunction "30_30") (pintype "passive"))
      (node (ref "SV2") (pin "34") (pinfunction "34_34") (pintype "passive"))
      (node (ref "SV2") (pin "39") (pinfunction "39_39") (pintype "passive"))
      (node (ref "SV2") (pin "6") (pinfunction "6_6") (pintype "passive"))
      (node (ref "SV2") (pin "9") (pinfunction "9_9") (pintype "passive"))
      (node (ref "U$1") (pin "6") (pinfunction "VSS_6") (pintype "power_in"))
      (node (ref "U$1") (pin "MT1") (pinfunction "GND_MT1") (pintype "power_in"))
      (node (ref "U$1") (pin "MT2") (pinfunction "GND1_MT2") (pintype "power_in"))
      (node (ref "U$2") (pin "1") (pinfunction "GND1_1") (pintype "bidirectional"))
      (node (ref "U$2") (pin "15") (pinfunction "GND4_15") (pintype "bidirectional"))
      (node (ref "U$2") (pin "21") (pinfunction "GND5_21") (pintype "bidirectional"))
      (node (ref "U$2") (pin "27") (pinfunction "GND6_27") (pintype "bidirectional"))
      (node (ref "U$2") (pin "3") (pinfunction "GND2_3") (pintype "bidirectional"))
      (node (ref "U$2") (pin "33") (pinfunction "GND7_33") (pintype "bidirectional"))
      (node (ref "U$2") (pin "39") (pinfunction "GND8_39") (pintype "bidirectional"))
      (node (ref "U$2") (pin "45") (pinfunction "GND9_45") (pintype "bidirectional"))
      (node (ref "U$2") (pin "51") (pinfunction "GND10_51") (pintype "bidirectional"))
      (node (ref "U$2") (pin "57") (pinfunction "GND11_57") (pintype "bidirectional"))
      (node (ref "U$2") (pin "71") (pinfunction "GND12_71") (pintype "bidirectional"))
      (node (ref "U$2") (pin "73") (pinfunction "GND13_73") (pintype "bidirectional"))
      (node (ref "U$2") (pin "75") (pinfunction "GND14_75") (pintype "bidirectional"))
      (node (ref "U$2") (pin "9") (pinfunction "GND3_9") (pintype "bidirectional"))
      (node (ref "U$2") (pin "S1") (pinfunction "S1_S1") (pintype "bidirectional"))
      (node (ref "U$2") (pin "S2") (pinfunction "S2_S2") (pintype "bidirectional"))
      (node (ref "X1") (pin "2") (pinfunction "GND_2") (pintype "power_in"))
    )
    (net (code "34") (name "GPIO2") (class "Default")
      (node (ref "J2") (pin "58") (pinfunction "58_58") (pintype "passive"))
      (node (ref "SV2") (pin "3") (pinfunction "3_3") (pintype "passive"))
    )
    (net (code "35") (name "GPIO3") (class "Default")
      (node (ref "J2") (pin "56") (pinfunction "56_56") (pintype "passive"))
      (node (ref "SV2") (pin "5") (pinfunction "5_5") (pintype "passive"))
    )
    (net (code "36") (name "GPIO4") (class "Default")
      (node (ref "J2") (pin "54") (pinfunction "54_54") (pintype "passive"))
      (node (ref "SV2") (pin "7") (pinfunction "7_7") (pintype "passive"))
    )
    (net (code "37") (name "GPIO5") (class "Default")
      (node (ref "J2") (pin "34") (pinfunction "34_34") (pintype "passive"))
      (node (ref "SV2") (pin "29") (pinfunction "29_29") (pintype "passive"))
    )
    (net (code "38") (name "GPIO6") (class "Default")
      (node (ref "J2") (pin "30") (pinfunction "30_30") (pintype "passive"))
      (node (ref "SV2") (pin "31") (pinfunction "31_31") (pintype "passive"))
    )
    (net (code "39") (name "GPIO7") (class "Default")
      (node (ref "J2") (pin "37") (pinfunction "37_37") (pintype "passive"))
      (node (ref "SV2") (pin "26") (pinfunction "26_26") (pintype "passive"))
    )
    (net (code "40") (name "GPIO8") (class "Default")
      (node (ref "J2") (pin "39") (pinfunction "39_39") (pintype "passive"))
      (node (ref "SV2") (pin "24") (pinfunction "24_24") (pintype "passive"))
    )
    (net (code "41") (name "GPIO9") (class "Default")
      (node (ref "J2") (pin "40") (pinfunction "40_40") (pintype "passive"))
      (node (ref "SV2") (pin "21") (pinfunction "21_21") (pintype "passive"))
    )
    (net (code "42") (name "GPIO10") (class "Default")
      (node (ref "J2") (pin "44") (pinfunction "44_44") (pintype "passive"))
      (node (ref "SV2") (pin "19") (pinfunction "19_19") (pintype "passive"))
    )
    (net (code "43") (name "GPIO11") (class "Default")
      (node (ref "J2") (pin "38") (pinfunction "38_38") (pintype "passive"))
      (node (ref "SV2") (pin "23") (pinfunction "23_23") (pintype "passive"))
    )
    (net (code "44") (name "GPIO12") (class "Default")
      (node (ref "J2") (pin "31") (pinfunction "31_31") (pintype "passive"))
      (node (ref "SV2") (pin "32") (pinfunction "32_32") (pintype "passive"))
    )
    (net (code "45") (name "GPIO13") (class "Default")
      (node (ref "J2") (pin "28") (pinfunction "28_28") (pintype "passive"))
      (node (ref "SV2") (pin "33") (pinfunction "33_33") (pintype "passive"))
    )
    (net (code "46") (name "GPIO14") (class "Default")
      (node (ref "J2") (pin "55") (pinfunction "55_55") (pintype "passive"))
      (node (ref "SV2") (pin "8") (pinfunction "8_8") (pintype "passive"))
    )
    (net (code "47") (name "GPIO15") (class "Default")
      (node (ref "J2") (pin "51") (pinfunction "51_51") (pintype "passive"))
      (node (ref "SV2") (pin "10") (pinfunction "10_10") (pintype "passive"))
    )
    (net (code "48") (name "GPIO16") (class "Default")
      (node (ref "J2") (pin "29") (pinfunction "29_29") (pintype "passive"))
      (node (ref "SV2") (pin "36") (pinfunction "36_36") (pintype "passive"))
    )
    (net (code "49") (name "GPIO17") (class "Default")
      (node (ref "J2") (pin "50") (pinfunction "50_50") (pintype "passive"))
      (node (ref "SV2") (pin "11") (pinfunction "11_11") (pintype "passive"))
    )
    (net (code "50") (name "GPIO18") (class "Default")
      (node (ref "J2") (pin "49") (pinfunction "49_49") (pintype "passive"))
      (node (ref "SV2") (pin "12") (pinfunction "12_12") (pintype "passive"))
    )
    (net (code "51") (name "GPIO19") (class "Default")
      (node (ref "J2") (pin "26") (pinfunction "26_26") (pintype "passive"))
      (node (ref "SV2") (pin "35") (pinfunction "35_35") (pintype "passive"))
    )
    (net (code "52") (name "GPIO20") (class "Default")
      (node (ref "J2") (pin "27") (pinfunction "27_27") (pintype "passive"))
      (node (ref "SV2") (pin "38") (pinfunction "38_38") (pintype "passive"))
    )
    (net (code "53") (name "GPIO21") (class "Default")
      (node (ref "J2") (pin "25") (pinfunction "25_25") (pintype "passive"))
      (node (ref "SV2") (pin "40") (pinfunction "40_40") (pintype "passive"))
    )
    (net (code "54") (name "GPIO22") (class "Default")
      (node (ref "J2") (pin "46") (pinfunction "46_46") (pintype "passive"))
      (node (ref "SV2") (pin "15") (pinfunction "15_15") (pintype "passive"))
    )
    (net (code "55") (name "GPIO23") (class "Default")
      (node (ref "J2") (pin "47") (pinfunction "47_47") (pintype "passive"))
      (node (ref "SV2") (pin "16") (pinfunction "16_16") (pintype "passive"))
    )
    (net (code "56") (name "GPIO24") (class "Default")
      (node (ref "J2") (pin "45") (pinfunction "45_45") (pintype "passive"))
      (node (ref "SV2") (pin "18") (pinfunction "18_18") (pintype "passive"))
    )
    (net (code "57") (name "GPIO25") (class "Default")
      (node (ref "J2") (pin "41") (pinfunction "41_41") (pintype "passive"))
      (node (ref "SV2") (pin "22") (pinfunction "22_22") (pintype "passive"))
    )
    (net (code "58") (name "GPIO26") (class "Default")
      (node (ref "J2") (pin "24") (pinfunction "24_24") (pintype "passive"))
      (node (ref "SV2") (pin "37") (pinfunction "37_37") (pintype "passive"))
    )
    (net (code "59") (name "GPIO27") (class "Default")
      (node (ref "J2") (pin "48") (pinfunction "48_48") (pintype "passive"))
      (node (ref "SV2") (pin "13") (pinfunction "13_13") (pintype "passive"))
    )
    (net (code "60") (name "GPIO_VREF") (class "Default")
      (node (ref "J2") (pin "78") (pinfunction "78_78") (pintype "passive"))
      (node (ref "R3") (pin "1") (pinfunction "1_1") (pintype "passive"))
      (node (ref "R4") (pin "1") (pinfunction "1_1") (pintype "passive"))
      (node (ref "R6") (pin "2") (pinfunction "2_2") (pintype "passive"))
      (node (ref "R7") (pin "2") (pinfunction "2_2") (pintype "passive"))
    )
    (net (code "61") (name "HDMI0_CEC") (class "Default")
      (node (ref "J1") (pin "51") (pinfunction "51_51") (pintype "passive"))
      (node (ref "J4") (pin "13") (pinfunction "GROUND_13") (pintype "passive"))
    )
    (net (code "62") (name "HDMI0_CK_N") (class "Default")
      (node (ref "J1") (pin "90") (pinfunction "90_90") (pintype "passive"))
      (node (ref "J4") (pin "12") (pinfunction "TMDSCLOCK-_12") (pintype "passive"))
    )
    (net (code "63") (name "HDMI0_CK_P") (class "Default")
      (node (ref "J1") (pin "88") (pinfunction "88_88") (pintype "passive"))
      (node (ref "J4") (pin "10") (pinfunction "TMDSCLOCKSHIELD_10") (pintype "passive"))
    )
    (net (code "64") (name "HDMI0_D0_N") (class "Default")
      (node (ref "J1") (pin "84") (pinfunction "84_84") (pintype "passive"))
      (node (ref "J4") (pin "9") (pinfunction "TMDS0-_9") (pintype "passive"))
    )
    (net (code "65") (name "HDMI0_D0_P") (class "Default")
      (node (ref "J1") (pin "82") (pinfunction "82_82") (pintype "passive"))
      (node (ref "J4") (pin "7") (pinfunction "TMDS0SHIELD_7") (pintype "passive"))
    )
    (net (code "66") (name "HDMI0_D1_N") (class "Default")
      (node (ref "J1") (pin "78") (pinfunction "78_78") (pintype "passive"))
      (node (ref "J4") (pin "6") (pinfunction "TMDS1-_6") (pintype "passive"))
    )
    (net (code "67") (name "HDMI0_D1_P") (class "Default")
      (node (ref "J1") (pin "76") (pinfunction "76_76") (pintype "passive"))
      (node (ref "J4") (pin "4") (pinfunction "TMDS1SHIELD_4") (pintype "passive"))
    )
    (net (code "68") (name "HDMI0_D2_N") (class "Default")
      (node (ref "J1") (pin "72") (pinfunction "72_72") (pintype "passive"))
      (node (ref "J4") (pin "3") (pinfunction "TMDS2-_3") (pintype "passive"))
    )
    (net (code "69") (name "HDMI0_D2_P") (class "Default")
      (node (ref "J1") (pin "70") (pinfunction "70_70") (pintype "passive"))
      (node (ref "J4") (pin "1") (pinfunction "TMDS2SHIELD_1") (pintype "passive"))
    )
    (net (code "70") (name "HDMI0_HOTPLUG") (class "Default")
      (node (ref "J1") (pin "53") (pinfunction "53_53") (pintype "passive"))
      (node (ref "J4") (pin "19") (pinfunction "HOTPLUG/HEC+_19") (pintype "passive"))
    )
    (net (code "71") (name "HDMI0_SCL") (class "Default")
      (node (ref "J1") (pin "100") (pinfunction "100_100") (pintype "passive"))
      (node (ref "J4") (pin "15") (pinfunction "SCL_15") (pintype "passive"))
    )
    (net (code "72") (name "HDMI0_SDA") (class "Default")
      (node (ref "J1") (pin "99") (pinfunction "99_99") (pintype "passive"))
      (node (ref "J4") (pin "16") (pinfunction "SDA_16") (pintype "passive"))
    )
    (net (code "73") (name "HDMI1_CEC") (class "Default")
      (node (ref "J1") (pin "49") (pinfunction "49_49") (pintype "passive"))
      (node (ref "J5") (pin "13") (pinfunction "GROUND_13") (pintype "passive"))
    )
    (net (code "74") (name "HDMI1_CK_N") (class "Default")
      (node (ref "J1") (pin "66") (pinfunction "66_66") (pintype "passive"))
      (node (ref "J5") (pin "12") (pinfunction "TMDSCLOCK-_12") (pintype "passive"))
    )
    (net (code "75") (name "HDMI1_CK_P") (class "Default")
      (node (ref "J1") (pin "64") (pinfunction "64_64") (pintype "passive"))
      (node (ref "J5") (pin "10") (pinfunction "TMDSCLOCKSHIELD_10") (pintype "passive"))
    )
    (net (code "76") (name "HDMI1_D0_N") (class "Default")
      (node (ref "J1") (pin "60") (pinfunction "60_60") (pintype "passive"))
      (node (ref "J5") (pin "9") (pinfunction "TMDS0-_9") (pintype "passive"))
    )
    (net (code "77") (name "HDMI1_D0_P") (class "Default")
      (node (ref "J1") (pin "58") (pinfunction "58_58") (pintype "passive"))
      (node (ref "J5") (pin "7") (pinfunction "TMDS0SHIELD_7") (pintype "passive"))
    )
    (net (code "78") (name "HDMI1_D1_N") (class "Default")
      (node (ref "J1") (pin "54") (pinfunction "54_54") (pintype "passive"))
      (node (ref "J5") (pin "6") (pinfunction "TMDS1-_6") (pintype "passive"))
    )
    (net (code "79") (name "HDMI1_D1_P") (class "Default")
      (node (ref "J1") (pin "52") (pinfunction "52_52") (pintype "passive"))
      (node (ref "J5") (pin "4") (pinfunction "TMDS1SHIELD_4") (pintype "passive"))
    )
    (net (code "80") (name "HDMI1_D2_N") (class "Default")
      (node (ref "J1") (pin "48") (pinfunction "48_48") (pintype "passive"))
      (node (ref "J5") (pin "3") (pinfunction "TMDS2-_3") (pintype "passive"))
    )
    (net (code "81") (name "HDMI1_D2_P") (class "Default")
      (node (ref "J1") (pin "46") (pinfunction "46_46") (pintype "passive"))
      (node (ref "J5") (pin "1") (pinfunction "TMDS2SHIELD_1") (pintype "passive"))
    )
    (net (code "82") (name "HDMI1_HOTPLUG") (class "Default")
      (node (ref "J1") (pin "43") (pinfunction "43_43") (pintype "passive"))
      (node (ref "J5") (pin "19") (pinfunction "HOTPLUG/HEC+_19") (pintype "passive"))
    )
    (net (code "83") (name "HDMI1_SCL") (class "Default")
      (node (ref "J1") (pin "47") (pinfunction "47_47") (pintype "passive"))
      (node (ref "J5") (pin "15") (pinfunction "SCL_15") (pintype "passive"))
    )
    (net (code "84") (name "HDMI1_SDA") (class "Default")
      (node (ref "J1") (pin "45") (pinfunction "45_45") (pintype "passive"))
      (node (ref "J5") (pin "16") (pinfunction "SDA_16") (pintype "passive"))
    )
    (net (code "85") (name "HDMI_5V") (class "Default")
      (node (ref "C4") (pin "1") (pinfunction "1_1") (pintype "passive"))
      (node (ref "IC4") (pin "2") (pinfunction "OUT_2") (pintype "power_in"))
      (node (ref "J4") (pin "18") (pinfunction "POWER_18") (pintype "power_in"))
      (node (ref "J5") (pin "18") (pinfunction "POWER_18") (pintype "power_in"))
    )
    (net (code "86") (name "ID_SC") (class "Default")
      (node (ref "J2") (pin "35") (pinfunction "35_35") (pintype "passive"))
      (node (ref "JP1") (pin "1") (pinfunction "1_1") (pintype "passive"))
      (node (ref "SV2") (pin "28") (pinfunction "28_28") (pintype "passive"))
    )
    (net (code "87") (name "ID_SD") (class "Default")
      (node (ref "J2") (pin "36") (pinfunction "36_36") (pintype "passive"))
      (node (ref "JP1") (pin "3") (pinfunction "3_3") (pintype "passive"))
      (node (ref "SV2") (pin "27") (pinfunction "27_27") (pintype "passive"))
    )
    (net (code "88") (name "LED_NACT") (class "Default")
      (node (ref "J2") (pin "21") (pinfunction "21_21") (pintype "passive"))
    )
    (net (code "89") (name "M2_3V3") (class "Default")
      (node (ref "C12") (pin "1") (pinfunction "1_1") (pintype "passive"))
      (node (ref "C13") (pin "1") (pinfunction "1_1") (pintype "passive"))
      (node (ref "C14") (pin "1") (pinfunction "1_1") (pintype "passive"))
      (node (ref "C15") (pin "1") (pinfunction "1_1") (pintype "passive"))
      (node (ref "C16") (pin "1") (pinfunction "1_1") (pintype "passive"))
      (node (ref "C17") (pin "1") (pinfunction "1_1") (pintype "passive"))
      (node (ref "L1") (pin "2") (pinfunction "2_2") (pintype "passive"))
      (node (ref "R12") (pin "1") (pinfunction "1_1") (pintype "passive"))
      (node (ref "U$2") (pin "12") (pinfunction "VCC3_12") (pintype "bidirectional"))
      (node (ref "U$2") (pin "14") (pinfunction "VCC4_14") (pintype "bidirectional"))
      (node (ref "U$2") (pin "16") (pinfunction "VCC5_16") (pintype "bidirectional"))
      (node (ref "U$2") (pin "18") (pinfunction "VCC6_18") (pintype "bidirectional"))
      (node (ref "U$2") (pin "2") (pinfunction "VCC1_2") (pintype "bidirectional"))
      (node (ref "U$2") (pin "4") (pinfunction "VCC2_4") (pintype "bidirectional"))
      (node (ref "U$2") (pin "70") (pinfunction "VCC7_70") (pintype "bidirectional"))
      (node (ref "U$2") (pin "72") (pinfunction "VCC8_72") (pintype "bidirectional"))
      (node (ref "U$2") (pin "74") (pinfunction "VCC9_74") (pintype "bidirectional"))
      (node (ref "X1") (pin "1") (pinfunction "TS_1") (pintype "passive"))
      (node (ref "X1") (pin "4") (pinfunction "VDD_4") (pintype "power_in"))
    )
    (net (code "90") (name "NPWR_LED") (class "Default")
      (node (ref "IC3") (pin "2") (pinfunction "A_2") (pintype "input"))
      (node (ref "J2") (pin "95") (pinfunction "95_95") (pintype "passive"))
    )
    (net (code "91") (name "NRPIBOOT") (class "Default")
      (node (ref "J2") (pin "93") (pinfunction "93_93") (pintype "passive"))
      (node (ref "JP2") (pin "2") (pinfunction "2_2") (pintype "passive"))
    )
    (net (code "92") (name "Net-(C11-Pad1)") (class "Default")
      (node (ref "C11") (pin "1") (pinfunction "1_1") (pintype "passive"))
      (node (ref "ETH1") (pin "P1") (pinfunction "P1_P1") (pintype "bidirectional"))
      (node (ref "ETH1") (pin "P10") (pinfunction "P10_P10") (pintype "bidirectional"))
    )
    (net (code "93") (name "Net-(ETH1-PadP12)") (class "Default")
      (node (ref "ETH1") (pin "P12") (pinfunction "P12_P12") (pintype "bidirectional"))
      (node (ref "R8") (pin "2") (pinfunction "2_2") (pintype "passive"))
    )
    (net (code "94") (name "Net-(ETH1-PadP13)") (class "Default")
      (node (ref "ETH1") (pin "P13") (pinfunction "P13_P13") (pintype "bidirectional"))
      (node (ref "R9") (pin "1") (pinfunction "1_1") (pintype "passive"))
    )
    (net (code "95") (name "Net-(IC2-ILIM)") (class "Default")
      (node (ref "IC2") (pin "5") (pinfunction "ILIM_5") (pintype "bidirectional"))
      (node (ref "R2") (pin "1") (pinfunction "1_1") (pintype "passive"))
    )
    (net (code "96") (name "Net-(IC3-Y)") (class "Default")
      (node (ref "IC3") (pin "4") (pinfunction "Y_4") (pintype "output"))
      (node (ref "R5") (pin "2") (pinfunction "2_2") (pintype "passive"))
    )
    (net (code "97") (name "Net-(IC5-FB)") (class "Default")
      (node (ref "C13") (pin "2") (pinfunction "2_2") (pintype "passive"))
      (node (ref "IC5") (pin "1") (pinfunction "FB_1") (pintype "bidirectional"))
      (node (ref "R12") (pin "2") (pinfunction "2_2") (pintype "passive"))
      (node (ref "R13") (pin "1") (pinfunction "1_1") (pintype "passive"))
    )
    (net (code "98") (name "Net-(IC5-LX)") (class "Default")
      (node (ref "IC5") (pin "6") (pinfunction "LX_6") (pintype "power_in"))
      (node (ref "L1") (pin "1") (pinfunction "1_1") (pintype "passive"))
    )
    (net (code "99") (name "Net-(LED1-PadC)") (class "Default")
      (node (ref "LED1") (pin "C") (pinfunction "C_C") (pintype "passive"))
      (node (ref "R5") (pin "1") (pinfunction "1_1") (pintype "passive"))
    )
    (net (code "100") (name "Net-(LED2-PadC)") (class "Default")
      (node (ref "LED2") (pin "C") (pinfunction "C_C") (pintype "passive"))
      (node (ref "R10") (pin "1") (pinfunction "1_1") (pintype "passive"))
    )
    (net (code "101") (name "Net-(U$2-DA5{slash}~{DSS}{slash}~{LED1})") (class "Default")
      (node (ref "R10") (pin "2") (pinfunction "2_2") (pintype "passive"))
      (node (ref "U$2") (pin "10") (pinfunction "DA5/~{DSS}/~{LED1}_10") (pintype "bidirectional"))
    )
    (net (code "102") (name "Net-(U$2-SUSCLK)") (class "Default")
      (node (ref "U$2") (pin "68") (pinfunction "SUSCLK_68") (pintype "bidirectional"))
      (node (ref "X1") (pin "3") (pinfunction "OUT_3") (pintype "output"))
    )
    (net (code "103") (name "PCIE_CLK_N") (class "Default")
      (node (ref "J1") (pin "12") (pinfunction "12_12") (pintype "passive"))
      (node (ref "U$2") (pin "53") (pinfunction "REFCLK_N_53") (pintype "bidirectional"))
    )
    (net (code "104") (name "PCIE_CLK_P") (class "Default")
      (node (ref "J1") (pin "10") (pinfunction "10_10") (pintype "passive"))
      (node (ref "U$2") (pin "55") (pinfunction "REFCLK_P_55") (pintype "bidirectional"))
    )
    (net (code "105") (name "PCIE_NCLKREQ") (class "Default")
      (node (ref "J1") (pin "2") (pinfunction "2_2") (pintype "passive"))
      (node (ref "U$2") (pin "52") (pinfunction "~{CLKREQ}_52") (pintype "bidirectional"))
    )
    (net (code "106") (name "PCIE_NRST") (class "Default")
      (node (ref "J1") (pin "9") (pinfunction "9_9") (pintype "passive"))
      (node (ref "U$2") (pin "50") (pinfunction "~{PERST}_50") (pintype "bidirectional"))
    )
    (net (code "107") (name "PCIE_NWAKE") (class "Default")
      (node (ref "J1") (pin "4") (pinfunction "4_4") (pintype "passive"))
      (node (ref "U$2") (pin "54") (pinfunction "~{PEWAKE}_54") (pintype "bidirectional"))
    )
    (net (code "108") (name "PCIE_PWR_EN") (class "Default")
      (node (ref "IC5") (pin "7") (pinfunction "EN_7") (pintype "bidirectional"))
      (node (ref "J1") (pin "6") (pinfunction "6_6") (pintype "passive"))
      (node (ref "R11") (pin "1") (pinfunction "1_1") (pintype "passive"))
    )
    (net (code "109") (name "PCIE_RX_N") (class "Default")
      (node (ref "J1") (pin "18") (pinfunction "18_18") (pintype "passive"))
      (node (ref "U$2") (pin "43") (pinfunction "PET_P0_43") (pintype "bidirectional"))
    )
    (net (code "110") (name "PCIE_RX_P") (class "Default")
      (node (ref "J1") (pin "16") (pinfunction "16_16") (pintype "passive"))
      (node (ref "U$2") (pin "41") (pinfunction "PET_N0_41") (pintype "bidirectional"))
    )
    (net (code "111") (name "PCIE_TX_N") (class "Default")
      (node (ref "J1") (pin "24") (pinfunction "24_24") (pintype "passive"))
      (node (ref "U$2") (pin "49") (pinfunction "PER_P0_49") (pintype "bidirectional"))
    )
    (net (code "112") (name "PCIE_TX_P") (class "Default")
      (node (ref "J1") (pin "22") (pinfunction "22_22") (pintype "passive"))
      (node (ref "U$2") (pin "47") (pinfunction "PER_N0_47") (pintype "bidirectional"))
    )
    (net (code "113") (name "PMIC_ENABLE") (class "Default")
      (node (ref "J2") (pin "99") (pinfunction "99_99") (pintype "passive"))
      (node (ref "JP2") (pin "12") (pinfunction "12_12") (pintype "passive"))
    )
    (net (code "114") (name "PWM") (class "Default")
      (node (ref "J2") (pin "19") (pinfunction "19_19") (pintype "passive"))
      (node (ref "SV1") (pin "3") (pinfunction "3_3") (pintype "passive"))
    )
    (net (code "115") (name "PWR_BUT") (class "Default")
      (node (ref "J2") (pin "92") (pinfunction "92_92") (pintype "passive"))
      (node (ref "JP2") (pin "14") (pinfunction "14_14") (pintype "passive"))
      (node (ref "S1") (pin "1") (pinfunction "P_1") (pintype "passive"))
    )
    (net (code "116") (name "SCL0") (class "Default")
      (node (ref "J2") (pin "80") (pinfunction "80_80") (pintype "passive"))
    )
    (net (code "117") (name "SCL1") (class "Default")
      (node (ref "JP1") (pin "2") (pinfunction "2_2") (pintype "passive"))
      (node (ref "R4") (pin "2") (pinfunction "2_2") (pintype "passive"))
    )
    (net (code "118") (name "SDA0") (class "Default")
      (node (ref "J2") (pin "82") (pinfunction "82_82") (pintype "passive"))
    )
    (net (code "119") (name "SDA1") (class "Default")
      (node (ref "JP1") (pin "4") (pinfunction "4_4") (pintype "passive"))
      (node (ref "R3") (pin "2") (pinfunction "2_2") (pintype "passive"))
    )
    (net (code "120") (name "SD_CLK") (class "Default")
      (node (ref "J2") (pin "57") (pinfunction "57_57") (pintype "passive"))
      (node (ref "U$1") (pin "5") (pinfunction "SCLK_5") (pintype "input"))
    )
    (net (code "121") (name "SD_CMD") (class "Default")
      (node (ref "J2") (pin "62") (pinfunction "62_62") (pintype "passive"))
      (node (ref "U$1") (pin "3") (pinfunction "DATA_IN_3") (pintype "input"))
    )
    (net (code "122") (name "SD_DAT0") (class "Default")
      (node (ref "J2") (pin "63") (pinfunction "63_63") (pintype "passive"))
      (node (ref "U$1") (pin "7") (pinfunction "DATA_OUT_7") (pintype "output"))
    )
    (net (code "123") (name "SD_DAT1") (class "Default")
      (node (ref "J2") (pin "67") (pinfunction "67_67") (pintype "passive"))
      (node (ref "U$1") (pin "8") (pinfunction "DAT1_8") (pintype "bidirectional"))
    )
    (net (code "124") (name "SD_DAT2") (class "Default")
      (node (ref "J2") (pin "69") (pinfunction "69_69") (pintype "passive"))
      (node (ref "U$1") (pin "1") (pinfunction "DAT2_1") (pintype "bidirectional"))
    )
    (net (code "125") (name "SD_DAT3") (class "Default")
      (node (ref "J2") (pin "61") (pinfunction "61_61") (pintype "passive"))
      (node (ref "U$1") (pin "2") (pinfunction "CS_2") (pintype "input"))
    )
    (net (code "126") (name "SD_PWR") (class "Default")
      (node (ref "C10") (pin "1") (pinfunction "1_1") (pintype "passive"))
      (node (ref "IC1") (pin "1") (pinfunction "OUT_1") (pintype "power_in"))
      (node (ref "U$1") (pin "4") (pinfunction "VDD_4") (pintype "power_in"))
    )
    (net (code "127") (name "SD_PWR_ON") (class "Default")
      (node (ref "IC1") (pin "4") (pinfunction "EN_4") (pintype "bidirectional"))
      (node (ref "J2") (pin "75") (pinfunction "75_75") (pintype "passive"))
    )
    (net (code "128") (name "SYNC_OUT") (class "Default")
      (node (ref "J2") (pin "18") (pinfunction "18_18") (pintype "passive"))
      (node (ref "JP2") (pin "6") (pinfunction "6_6") (pintype "passive"))
    )
    (net (code "129") (name "TACHO") (class "Default")
      (node (ref "J2") (pin "16") (pinfunction "16_16") (pintype "passive"))
      (node (ref "SV1") (pin "1") (pinfunction "1_1") (pintype "passive"))
    )
    (net (code "130") (name "TRD0_N") (class "Default")
      (node (ref "D2") (pin "2") (pinfunction "D1-_2") (pintype "bidirectional"))
      (node (ref "D2") (pin "9") (pinfunction "D1-_9") (pintype "bidirectional"))
      (node (ref "ETH1") (pin "P3") (pinfunction "P3_P3") (pintype "bidirectional"))
      (node (ref "J2") (pin "10") (pinfunction "10_10") (pintype "passive"))
    )
    (net (code "131") (name "TRD0_P") (class "Default")
      (node (ref "D2") (pin "1") (pinfunction "D1+_1") (pintype "bidirectional"))
      (node (ref "D2") (pin "10") (pinfunction "D1+_10") (pintype "bidirectional"))
      (node (ref "ETH1") (pin "P2") (pinfunction "P2_P2") (pintype "bidirectional"))
      (node (ref "J2") (pin "12") (pinfunction "12_12") (pintype "passive"))
    )
    (net (code "132") (name "TRD1_N") (class "Default")
      (node (ref "D2") (pin "4") (pinfunction "D2+_4") (pintype "bidirectional"))
      (node (ref "D2") (pin "7") (pinfunction "D2+_7") (pintype "bidirectional"))
      (node (ref "ETH1") (pin "P5") (pinfunction "P5_P5") (pintype "bidirectional"))
      (node (ref "J2") (pin "6") (pinfunction "6_6") (pintype "passive"))
    )
    (net (code "133") (name "TRD1_P") (class "Default")
      (node (ref "D2") (pin "5") (pinfunction "D2-_5") (pintype "bidirectional"))
      (node (ref "D2") (pin "6") (pinfunction "D2-_6") (pintype "bidirectional"))
      (node (ref "ETH1") (pin "P4") (pinfunction "P4_P4") (pintype "bidirectional"))
      (node (ref "J2") (pin "4") (pinfunction "4_4") (pintype "passive"))
    )
    (net (code "134") (name "TRD2_N") (class "Default")
      (node (ref "D1") (pin "2") (pinfunction "D1-_2") (pintype "bidirectional"))
      (node (ref "D1") (pin "9") (pinfunction "D1-_9") (pintype "bidirectional"))
      (node (ref "ETH1") (pin "P7") (pinfunction "P7_P7") (pintype "bidirectional"))
      (node (ref "J2") (pin "9") (pinfunction "9_9") (pintype "passive"))
    )
    (net (code "135") (name "TRD2_P") (class "Default")
      (node (ref "D1") (pin "1") (pinfunction "D1+_1") (pintype "bidirectional"))
      (node (ref "D1") (pin "10") (pinfunction "D1+_10") (pintype "bidirectional"))
      (node (ref "ETH1") (pin "P6") (pinfunction "P6_P6") (pintype "bidirectional"))
      (node (ref "J2") (pin "11") (pinfunction "11_11") (pintype "passive"))
    )
    (net (code "136") (name "TRD3_N") (class "Default")
      (node (ref "D1") (pin "4") (pinfunction "D2+_4") (pintype "bidirectional"))
      (node (ref "D1") (pin "7") (pinfunction "D2+_7") (pintype "bidirectional"))
      (node (ref "ETH1") (pin "P9") (pinfunction "P9_P9") (pintype "bidirectional"))
      (node (ref "J2") (pin "5") (pinfunction "5_5") (pintype "passive"))
    )
    (net (code "137") (name "TRD3_P") (class "Default")
      (node (ref "D1") (pin "5") (pinfunction "D2-_5") (pintype "bidirectional"))
      (node (ref "D1") (pin "6") (pinfunction "D2-_6") (pintype "bidirectional"))
      (node (ref "ETH1") (pin "P8") (pinfunction "P8_P8") (pintype "bidirectional"))
      (node (ref "J2") (pin "3") (pinfunction "3_3") (pintype "passive"))
    )
    (net (code "138") (name "USB2_N") (class "Default")
      (node (ref "J1") (pin "3") (pinfunction "3_3") (pintype "passive"))
      (node (ref "J6") (pin "A7") (pinfunction "D-1_A7") (pintype "passive"))
      (node (ref "J6") (pin "B7") (pinfunction "D-2_B7") (pintype "passive"))
    )
    (net (code "139") (name "USB2_P") (class "Default")
      (node (ref "J1") (pin "5") (pinfunction "5_5") (pintype "passive"))
      (node (ref "J6") (pin "A6") (pinfunction "D+1_A6") (pintype "passive"))
      (node (ref "J6") (pin "B6") (pinfunction "D+2_B6") (pintype "passive"))
    )
    (net (code "140") (name "USB3-0-D_N") (class "Default")
      (node (ref "J1") (pin "36") (pinfunction "36_36") (pintype "passive"))
      (node (ref "J3") (pin "2") (pinfunction "D-_2") (pintype "passive"))
    )
    (net (code "141") (name "USB3-0-D_P") (class "Default")
      (node (ref "J1") (pin "34") (pinfunction "34_34") (pintype "passive"))
      (node (ref "J3") (pin "3") (pinfunction "D+_3") (pintype "passive"))
    )
    (net (code "142") (name "USB3-0-RX_N") (class "Default")
      (node (ref "J1") (pin "28") (pinfunction "28_28") (pintype "passive"))
      (node (ref "J3") (pin "5") (pinfunction "STDA_SSRX-_5") (pintype "passive"))
    )
    (net (code "143") (name "USB3-0-RX_P") (class "Default")
      (node (ref "J1") (pin "30") (pinfunction "30_30") (pintype "passive"))
      (node (ref "J3") (pin "6") (pinfunction "STDA_SSRX+_6") (pintype "passive"))
    )
    (net (code "144") (name "USB3-0-TX_N") (class "Default")
      (node (ref "J1") (pin "40") (pinfunction "40_40") (pintype "passive"))
      (node (ref "J3") (pin "8") (pinfunction "STDA_SSTX-_8") (pintype "passive"))
    )
    (net (code "145") (name "USB3-0-TX_P") (class "Default")
      (node (ref "J1") (pin "42") (pinfunction "42_42") (pintype "passive"))
      (node (ref "J3") (pin "9") (pinfunction "STDA_SSTX+_9") (pintype "passive"))
    )
    (net (code "146") (name "USB3-1-D_N") (class "Default")
      (node (ref "J1") (pin "65") (pinfunction "65_65") (pintype "passive"))
      (node (ref "J3") (pin "11") (pinfunction "D-_11") (pintype "passive"))
    )
    (net (code "147") (name "USB3-1-D_P") (class "Default")
      (node (ref "J1") (pin "63") (pinfunction "63_63") (pintype "passive"))
      (node (ref "J3") (pin "12") (pinfunction "D+_12") (pintype "passive"))
    )
    (net (code "148") (name "USB3-1-RX_N") (class "Default")
      (node (ref "J1") (pin "57") (pinfunction "57_57") (pintype "passive"))
      (node (ref "J3") (pin "14") (pinfunction "STDA_SSRX-_14") (pintype "passive"))
    )
    (net (code "149") (name "USB3-1-RX_P") (class "Default")
      (node (ref "J1") (pin "59") (pinfunction "59_59") (pintype "passive"))
      (node (ref "J3") (pin "15") (pinfunction "STDA_SSRX+_15") (pintype "passive"))
    )
    (net (code "150") (name "USB3-1-TX_N") (class "Default")
      (node (ref "J1") (pin "69") (pinfunction "69_69") (pintype "passive"))
      (node (ref "J3") (pin "17") (pinfunction "STDA_SSTX-_17") (pintype "passive"))
    )
    (net (code "151") (name "USB3-1-TX_P") (class "Default")
      (node (ref "J1") (pin "71") (pinfunction "71_71") (pintype "passive"))
      (node (ref "J3") (pin "18") (pinfunction "STDA_SSTX+_18") (pintype "passive"))
    )
    (net (code "152") (name "USBOTG") (class "Default")
      (node (ref "JP2") (pin "10") (pinfunction "10_10") (pintype "passive"))
    )
    (net (code "153") (name "USBOTG_ID") (class "Default")
      (node (ref "J1") (pin "1") (pinfunction "1_1") (pintype "passive"))
    )
    (net (code "154") (name "VBAT") (class "Default")
      (node (ref "BT1") (pin "P1") (pinfunction "+_P1") (pintype "passive"))
      (node (ref "BT1") (pin "P2") (pinfunction "+_P2") (pintype "passive"))
      (node (ref "J2") (pin "76") (pinfunction "76_76") (pintype "passive"))
    )
    (net (code "155") (name "VBUS") (class "Default")
      (node (ref "C6") (pin "1") (pinfunction "1_1") (pintype "passive"))
      (node (ref "C7") (pin "1") (pinfunction "1_1") (pintype "passive"))
      (node (ref "C8") (pin "+") (pinfunction "+_+") (pintype "passive"))
      (node (ref "IC2") (pin "6") (pinfunction "OUT_6") (pintype "bidirectional"))
      (node (ref "J3") (pin "1") (pinfunction "VBUS_1") (pintype "passive"))
      (node (ref "J3") (pin "10") (pinfunction "VBUS_10") (pintype "passive"))
    )
    (net (code "156") (name "VBUS_EN") (class "Default")
      (node (ref "IC2") (pin "3") (pinfunction "EN_3") (pintype "bidirectional"))
      (node (ref "J1") (pin "11") (pinfunction "11_11") (pintype "passive"))
    )
    (net (code "157") (name "WL_NDIS") (class "Default")
      (node (ref "J2") (pin "89") (pinfunction "89_89") (pintype "passive"))
      (node (ref "JP3") (pin "1") (pinfunction "1_1") (pintype "passive"))
    )
    (net (code "158") (name "unconnected-(IC1-NFLG-Pad3)") (class "Default")
      (node (ref "IC1") (pin "3") (pinfunction "NFLG_3") (pintype "bidirectional"))
    )
    (net (code "159") (name "unconnected-(IC2-~{FAULT}-Pad4)") (class "Default")
      (node (ref "IC2") (pin "4") (pinfunction "~{FAULT}_4") (pintype "bidirectional"))
    )
    (net (code "160") (name "unconnected-(IC5-NC-Pad5)") (class "Default")
      (node (ref "IC5") (pin "5") (pinfunction "NC_5") (pintype "no_connect"))
    )
    (net (code "161") (name "unconnected-(IC5-PG-Pad2)") (class "Default")
      (node (ref "IC5") (pin "2") (pinfunction "PG_2") (pintype "bidirectional"))
    )
    (net (code "162") (name "unconnected-(J2-Pad64)") (class "Default")
      (node (ref "J2") (pin "64") (pinfunction "64_64") (pintype "passive"))
    )
    (net (code "163") (name "unconnected-(J2-Pad68)") (class "Default")
      (node (ref "J2") (pin "68") (pinfunction "68_68") (pintype "passive"))
    )
    (net (code "164") (name "unconnected-(J2-Pad70)") (class "Default")
      (node (ref "J2") (pin "70") (pinfunction "70_70") (pintype "passive"))
    )
    (net (code "165") (name "unconnected-(J2-Pad72)") (class "Default")
      (node (ref "J2") (pin "72") (pinfunction "72_72") (pintype "passive"))
    )
    (net (code "166") (name "unconnected-(J2-Pad73)") (class "Default")
      (node (ref "J2") (pin "73") (pinfunction "73_73") (pintype "passive"))
    )
    (net (code "167") (name "unconnected-(J4-CEC-Pad14)") (class "Default")
      (node (ref "J4") (pin "14") (pinfunction "CEC_14") (pintype "passive"))
    )
    (net (code "168") (name "unconnected-(J5-CEC-Pad14)") (class "Default")
      (node (ref "J5") (pin "14") (pinfunction "CEC_14") (pintype "passive"))
    )
    (net (code "169") (name "unconnected-(J6-SBU1-PadA8)") (class "Default")
      (node (ref "J6") (pin "A8") (pinfunction "SBU1_A8") (pintype "passive"))
    )
    (net (code "170") (name "unconnected-(J6-SBU2-PadB8)") (class "Default")
      (node (ref "J6") (pin "B8") (pinfunction "SBU2_B8") (pintype "passive"))
    )
    (net (code "171") (name "unconnected-(JP2-Pad8)") (class "Default")
      (node (ref "JP2") (pin "8") (pinfunction "8_8") (pintype "passive"))
    )
    (net (code "172") (name "unconnected-(U$1-CARD_DETECT-PadCD1)") (class "Default")
      (node (ref "U$1") (pin "CD1") (pinfunction "CARD_DETECT_CD1") (pintype "passive"))
    )
    (net (code "173") (name "unconnected-(U$1-CARD_DETECT1-PadCD2)") (class "Default")
      (node (ref "U$1") (pin "CD2") (pinfunction "CARD_DETECT1_CD2") (pintype "passive"))
    )
    (net (code "174") (name "unconnected-(U$2-DEVSLP-Pad38)") (class "Default")
      (node (ref "U$2") (pin "38") (pinfunction "DEVSLP_38") (pintype "bidirectional"))
    )
    (net (code "175") (name "unconnected-(U$2-NC1-Pad58)") (class "Default")
      (node (ref "U$2") (pin "58") (pinfunction "NC1_58") (pintype "bidirectional"))
    )
    (net (code "176") (name "unconnected-(U$2-NC2-Pad56)") (class "Default")
      (node (ref "U$2") (pin "56") (pinfunction "NC2_56") (pintype "bidirectional"))
    )
    (net (code "177") (name "unconnected-(U$2-NC3-Pad48)") (class "Default")
      (node (ref "U$2") (pin "48") (pinfunction "NC3_48") (pintype "bidirectional"))
    )
    (net (code "178") (name "unconnected-(U$2-NC4-Pad46)") (class "Default")
      (node (ref "U$2") (pin "46") (pinfunction "NC4_46") (pintype "bidirectional"))
    )
    (net (code "179") (name "unconnected-(U$2-NC5-Pad44)") (class "Default")
      (node (ref "U$2") (pin "44") (pinfunction "NC5_44") (pintype "bidirectional"))
    )
    (net (code "180") (name "unconnected-(U$2-NC6-Pad42)") (class "Default")
      (node (ref "U$2") (pin "42") (pinfunction "NC6_42") (pintype "bidirectional"))
    )
    (net (code "181") (name "unconnected-(U$2-NC7-Pad40)") (class "Default")
      (node (ref "U$2") (pin "40") (pinfunction "NC7_40") (pintype "bidirectional"))
    )
    (net (code "182") (name "unconnected-(U$2-NC8-Pad36)") (class "Default")
      (node (ref "U$2") (pin "36") (pinfunction "NC8_36") (pintype "bidirectional"))
    )
    (net (code "183") (name "unconnected-(U$2-NC9-Pad34)") (class "Default")
      (node (ref "U$2") (pin "34") (pinfunction "NC9_34") (pintype "bidirectional"))
    )
    (net (code "184") (name "unconnected-(U$2-NC10-Pad32)") (class "Default")
      (node (ref "U$2") (pin "32") (pinfunction "NC10_32") (pintype "bidirectional"))
    )
    (net (code "185") (name "unconnected-(U$2-NC11-Pad30)") (class "Default")
      (node (ref "U$2") (pin "30") (pinfunction "NC11_30") (pintype "bidirectional"))
    )
    (net (code "186") (name "unconnected-(U$2-NC12-Pad28)") (class "Default")
      (node (ref "U$2") (pin "28") (pinfunction "NC12_28") (pintype "bidirectional"))
    )
    (net (code "187") (name "unconnected-(U$2-NC13-Pad26)") (class "Default")
      (node (ref "U$2") (pin "26") (pinfunction "NC13_26") (pintype "bidirectional"))
    )
    (net (code "188") (name "unconnected-(U$2-NC14-Pad24)") (class "Default")
      (node (ref "U$2") (pin "24") (pinfunction "NC14_24") (pintype "bidirectional"))
    )
    (net (code "189") (name "unconnected-(U$2-NC15-Pad22)") (class "Default")
      (node (ref "U$2") (pin "22") (pinfunction "NC15_22") (pintype "bidirectional"))
    )
    (net (code "190") (name "unconnected-(U$2-NC16-Pad20)") (class "Default")
      (node (ref "U$2") (pin "20") (pinfunction "NC16_20") (pintype "bidirectional"))
    )
    (net (code "191") (name "unconnected-(U$2-NC17-Pad8)") (class "Default")
      (node (ref "U$2") (pin "8") (pinfunction "NC17_8") (pintype "bidirectional"))
    )
    (net (code "192") (name "unconnected-(U$2-NC18-Pad6)") (class "Default")
      (node (ref "U$2") (pin "6") (pinfunction "NC18_6") (pintype "bidirectional"))
    )
    (net (code "193") (name "unconnected-(U$2-NC19-Pad67)") (class "Default")
      (node (ref "U$2") (pin "67") (pinfunction "NC19_67") (pintype "bidirectional"))
    )
    (net (code "194") (name "unconnected-(U$2-PEDET-Pad69)") (class "Default")
      (node (ref "U$2") (pin "69") (pinfunction "PEDET_69") (pintype "bidirectional"))
    )
    (net (code "195") (name "unconnected-(U$2-PER_N1-Pad35)") (class "Default")
      (node (ref "U$2") (pin "35") (pinfunction "PER_N1_35") (pintype "bidirectional"))
    )
    (net (code "196") (name "unconnected-(U$2-PER_N2-Pad23)") (class "Default")
      (node (ref "U$2") (pin "23") (pinfunction "PER_N2_23") (pintype "bidirectional"))
    )
    (net (code "197") (name "unconnected-(U$2-PER_N3-Pad11)") (class "Default")
      (node (ref "U$2") (pin "11") (pinfunction "PER_N3_11") (pintype "bidirectional"))
    )
    (net (code "198") (name "unconnected-(U$2-PER_P1-Pad37)") (class "Default")
      (node (ref "U$2") (pin "37") (pinfunction "PER_P1_37") (pintype "bidirectional"))
    )
    (net (code "199") (name "unconnected-(U$2-PER_P2-Pad25)") (class "Default")
      (node (ref "U$2") (pin "25") (pinfunction "PER_P2_25") (pintype "bidirectional"))
    )
    (net (code "200") (name "unconnected-(U$2-PER_P3-Pad13)") (class "Default")
      (node (ref "U$2") (pin "13") (pinfunction "PER_P3_13") (pintype "bidirectional"))
    )
    (net (code "201") (name "unconnected-(U$2-PET_N1-Pad29)") (class "Default")
      (node (ref "U$2") (pin "29") (pinfunction "PET_N1_29") (pintype "bidirectional"))
    )
    (net (code "202") (name "unconnected-(U$2-PET_N2-Pad17)") (class "Default")
      (node (ref "U$2") (pin "17") (pinfunction "PET_N2_17") (pintype "bidirectional"))
    )
    (net (code "203") (name "unconnected-(U$2-PET_N3-Pad5)") (class "Default")
      (node (ref "U$2") (pin "5") (pinfunction "PET_N3_5") (pintype "bidirectional"))
    )
    (net (code "204") (name "unconnected-(U$2-PET_P1-Pad31)") (class "Default")
      (node (ref "U$2") (pin "31") (pinfunction "PET_P1_31") (pintype "bidirectional"))
    )
    (net (code "205") (name "unconnected-(U$2-PET_P2-Pad19)") (class "Default")
      (node (ref "U$2") (pin "19") (pinfunction "PET_P2_19") (pintype "bidirectional"))
    )
    (net (code "206") (name "unconnected-(U$2-PET_P3-Pad7)") (class "Default")
      (node (ref "U$2") (pin "7") (pinfunction "PET_P3_7") (pintype "bidirectional"))
    )
    (net (code "207") (name "unconnected-(U$3-DA5{slash}~{DSS}{slash}~{LED1}-Pad10)") (class "Default")
      (node (ref "U$3") (pin "10") (pinfunction "DA5/~{DSS}/~{LED1}_10") (pintype "bidirectional"))
    )
    (net (code "208") (name "unconnected-(U$3-DEVSLP-Pad38)") (class "Default")
      (node (ref "U$3") (pin "38") (pinfunction "DEVSLP_38") (pintype "bidirectional"))
    )
    (net (code "209") (name "unconnected-(U$3-GND1-Pad1)") (class "Default")
      (node (ref "U$3") (pin "1") (pinfunction "GND1_1") (pintype "bidirectional"))
    )
    (net (code "210") (name "unconnected-(U$3-GND2-Pad3)") (class "Default")
      (node (ref "U$3") (pin "3") (pinfunction "GND2_3") (pintype "bidirectional"))
    )
    (net (code "211") (name "unconnected-(U$3-GND3-Pad9)") (class "Default")
      (node (ref "U$3") (pin "9") (pinfunction "GND3_9") (pintype "bidirectional"))
    )
    (net (code "212") (name "unconnected-(U$3-GND4-Pad15)") (class "Default")
      (node (ref "U$3") (pin "15") (pinfunction "GND4_15") (pintype "bidirectional"))
    )
    (net (code "213") (name "unconnected-(U$3-GND5-Pad21)") (class "Default")
      (node (ref "U$3") (pin "21") (pinfunction "GND5_21") (pintype "bidirectional"))
    )
    (net (code "214") (name "unconnected-(U$3-GND6-Pad27)") (class "Default")
      (node (ref "U$3") (pin "27") (pinfunction "GND6_27") (pintype "bidirectional"))
    )
    (net (code "215") (name "unconnected-(U$3-GND7-Pad33)") (class "Default")
      (node (ref "U$3") (pin "33") (pinfunction "GND7_33") (pintype "bidirectional"))
    )
    (net (code "216") (name "unconnected-(U$3-GND8-Pad39)") (class "Default")
      (node (ref "U$3") (pin "39") (pinfunction "GND8_39") (pintype "bidirectional"))
    )
    (net (code "217") (name "unconnected-(U$3-GND9-Pad45)") (class "Default")
      (node (ref "U$3") (pin "45") (pinfunction "GND9_45") (pintype "bidirectional"))
    )
    (net (code "218") (name "unconnected-(U$3-GND10-Pad51)") (class "Default")
      (node (ref "U$3") (pin "51") (pinfunction "GND10_51") (pintype "bidirectional"))
    )
    (net (code "219") (name "unconnected-(U$3-GND11-Pad57)") (class "Default")
      (node (ref "U$3") (pin "57") (pinfunction "GND11_57") (pintype "bidirectional"))
    )
    (net (code "220") (name "unconnected-(U$3-GND12-Pad71)") (class "Default")
      (node (ref "U$3") (pin "71") (pinfunction "GND12_71") (pintype "bidirectional"))
    )
    (net (code "221") (name "unconnected-(U$3-GND13-Pad73)") (class "Default")
      (node (ref "U$3") (pin "73") (pinfunction "GND13_73") (pintype "bidirectional"))
    )
    (net (code "222") (name "unconnected-(U$3-GND14-Pad75)") (class "Default")
      (node (ref "U$3") (pin "75") (pinfunction "GND14_75") (pintype "bidirectional"))
    )
    (net (code "223") (name "unconnected-(U$3-NC1-Pad58)") (class "Default")
      (node (ref "U$3") (pin "58") (pinfunction "NC1_58") (pintype "bidirectional"))
    )
    (net (code "224") (name "unconnected-(U$3-NC2-Pad56)") (class "Default")
      (node (ref "U$3") (pin "56") (pinfunction "NC2_56") (pintype "bidirectional"))
    )
    (net (code "225") (name "unconnected-(U$3-NC3-Pad48)") (class "Default")
      (node (ref "U$3") (pin "48") (pinfunction "NC3_48") (pintype "bidirectional"))
    )
    (net (code "226") (name "unconnected-(U$3-NC4-Pad46)") (class "Default")
      (node (ref "U$3") (pin "46") (pinfunction "NC4_46") (pintype "bidirectional"))
    )
    (net (code "227") (name "unconnected-(U$3-NC5-Pad44)") (class "Default")
      (node (ref "U$3") (pin "44") (pinfunction "NC5_44") (pintype "bidirectional"))
    )
    (net (code "228") (name "unconnected-(U$3-NC6-Pad42)") (class "Default")
      (node (ref "U$3") (pin "42") (pinfunction "NC6_42") (pintype "bidirectional"))
    )
    (net (code "229") (name "unconnected-(U$3-NC7-Pad40)") (class "Default")
      (node (ref "U$3") (pin "40") (pinfunction "NC7_40") (pintype "bidirectional"))
    )
    (net (code "230") (name "unconnected-(U$3-NC8-Pad36)") (class "Default")
      (node (ref "U$3") (pin "36") (pinfunction "NC8_36") (pintype "bidirectional"))
    )
    (net (code "231") (name "unconnected-(U$3-NC9-Pad34)") (class "Default")
      (node (ref "U$3") (pin "34") (pinfunction "NC9_34") (pintype "bidirectional"))
    )
    (net (code "232") (name "unconnected-(U$3-NC10-Pad32)") (class "Default")
      (node (ref "U$3") (pin "32") (pinfunction "NC10_32") (pintype "bidirectional"))
    )
    (net (code "233") (name "unconnected-(U$3-NC11-Pad30)") (class "Default")
      (node (ref "U$3") (pin "30") (pinfunction "NC11_30") (pintype "bidirectional"))
    )
    (net (code "234") (name "unconnected-(U$3-NC12-Pad28)") (class "Default")
      (node (ref "U$3") (pin "28") (pinfunction "NC12_28") (pintype "bidirectional"))
    )
    (net (code "235") (name "unconnected-(U$3-NC13-Pad26)") (class "Default")
      (node (ref "U$3") (pin "26") (pinfunction "NC13_26") (pintype "bidirectional"))
    )
    (net (code "236") (name "unconnected-(U$3-NC14-Pad24)") (class "Default")
      (node (ref "U$3") (pin "24") (pinfunction "NC14_24") (pintype "bidirectional"))
    )
    (net (code "237") (name "unconnected-(U$3-NC15-Pad22)") (class "Default")
      (node (ref "U$3") (pin "22") (pinfunction "NC15_22") (pintype "bidirectional"))
    )
    (net (code "238") (name "unconnected-(U$3-NC16-Pad20)") (class "Default")
      (node (ref "U$3") (pin "20") (pinfunction "NC16_20") (pintype "bidirectional"))
    )
    (net (code "239") (name "unconnected-(U$3-NC17-Pad8)") (class "Default")
      (node (ref "U$3") (pin "8") (pinfunction "NC17_8") (pintype "bidirectional"))
    )
    (net (code "240") (name "unconnected-(U$3-NC18-Pad6)") (class "Default")
      (node (ref "U$3") (pin "6") (pinfunction "NC18_6") (pintype "bidirectional"))
    )
    (net (code "241") (name "unconnected-(U$3-NC19-Pad67)") (class "Default")
      (node (ref "U$3") (pin "67") (pinfunction "NC19_67") (pintype "bidirectional"))
    )
    (net (code "242") (name "unconnected-(U$3-PEDET-Pad69)") (class "Default")
      (node (ref "U$3") (pin "69") (pinfunction "PEDET_69") (pintype "bidirectional"))
    )
    (net (code "243") (name "unconnected-(U$3-PER_N0-Pad47)") (class "Default")
      (node (ref "U$3") (pin "47") (pinfunction "PER_N0_47") (pintype "bidirectional"))
    )
    (net (code "244") (name "unconnected-(U$3-PER_N1-Pad35)") (class "Default")
      (node (ref "U$3") (pin "35") (pinfunction "PER_N1_35") (pintype "bidirectional"))
    )
    (net (code "245") (name "unconnected-(U$3-PER_N2-Pad23)") (class "Default")
      (node (ref "U$3") (pin "23") (pinfunction "PER_N2_23") (pintype "bidirectional"))
    )
    (net (code "246") (name "unconnected-(U$3-PER_N3-Pad11)") (class "Default")
      (node (ref "U$3") (pin "11") (pinfunction "PER_N3_11") (pintype "bidirectional"))
    )
    (net (code "247") (name "unconnected-(U$3-PER_P0-Pad49)") (class "Default")
      (node (ref "U$3") (pin "49") (pinfunction "PER_P0_49") (pintype "bidirectional"))
    )
    (net (code "248") (name "unconnected-(U$3-PER_P1-Pad37)") (class "Default")
      (node (ref "U$3") (pin "37") (pinfunction "PER_P1_37") (pintype "bidirectional"))
    )
    (net (code "249") (name "unconnected-(U$3-PER_P2-Pad25)") (class "Default")
      (node (ref "U$3") (pin "25") (pinfunction "PER_P2_25") (pintype "bidirectional"))
    )
    (net (code "250") (name "unconnected-(U$3-PER_P3-Pad13)") (class "Default")
      (node (ref "U$3") (pin "13") (pinfunction "PER_P3_13") (pintype "bidirectional"))
    )
    (net (code "251") (name "unconnected-(U$3-PET_N0-Pad41)") (class "Default")
      (node (ref "U$3") (pin "41") (pinfunction "PET_N0_41") (pintype "bidirectional"))
    )
    (net (code "252") (name "unconnected-(U$3-PET_N1-Pad29)") (class "Default")
      (node (ref "U$3") (pin "29") (pinfunction "PET_N1_29") (pintype "bidirectional"))
    )
    (net (code "253") (name "unconnected-(U$3-PET_N2-Pad17)") (class "Default")
      (node (ref "U$3") (pin "17") (pinfunction "PET_N2_17") (pintype "bidirectional"))
    )
    (net (code "254") (name "unconnected-(U$3-PET_N3-Pad5)") (class "Default")
      (node (ref "U$3") (pin "5") (pinfunction "PET_N3_5") (pintype "bidirectional"))
    )
    (net (code "255") (name "unconnected-(U$3-PET_P0-Pad43)") (class "Default")
      (node (ref "U$3") (pin "43") (pinfunction "PET_P0_43") (pintype "bidirectional"))
    )
    (net (code "256") (name "unconnected-(U$3-PET_P1-Pad31)") (class "Default")
      (node (ref "U$3") (pin "31") (pinfunction "PET_P1_31") (pintype "bidirectional"))
    )
    (net (code "257") (name "unconnected-(U$3-PET_P2-Pad19)") (class "Default")
      (node (ref "U$3") (pin "19") (pinfunction "PET_P2_19") (pintype "bidirectional"))
    )
    (net (code "258") (name "unconnected-(U$3-PET_P3-Pad7)") (class "Default")
      (node (ref "U$3") (pin "7") (pinfunction "PET_P3_7") (pintype "bidirectional"))
    )
    (net (code "259") (name "unconnected-(U$3-PadS1)") (class "Default")
      (node (ref "U$3") (pin "S1") (pinfunction "S1_S1") (pintype "bidirectional"))
    )
    (net (code "260") (name "unconnected-(U$3-PadS2)") (class "Default")
      (node (ref "U$3") (pin "S2") (pinfunction "S2_S2") (pintype "bidirectional"))
    )
    (net (code "261") (name "unconnected-(U$3-REFCLK_N-Pad53)") (class "Default")
      (node (ref "U$3") (pin "53") (pinfunction "REFCLK_N_53") (pintype "bidirectional"))
    )
    (net (code "262") (name "unconnected-(U$3-REFCLK_P-Pad55)") (class "Default")
      (node (ref "U$3") (pin "55") (pinfunction "REFCLK_P_55") (pintype "bidirectional"))
    )
    (net (code "263") (name "unconnected-(U$3-SUSCLK-Pad68)") (class "Default")
      (node (ref "U$3") (pin "68") (pinfunction "SUSCLK_68") (pintype "bidirectional"))
    )
    (net (code "264") (name "unconnected-(U$3-VCC1-Pad2)") (class "Default")
      (node (ref "U$3") (pin "2") (pinfunction "VCC1_2") (pintype "bidirectional"))
    )
    (net (code "265") (name "unconnected-(U$3-VCC2-Pad4)") (class "Default")
      (node (ref "U$3") (pin "4") (pinfunction "VCC2_4") (pintype "bidirectional"))
    )
    (net (code "266") (name "unconnected-(U$3-VCC3-Pad12)") (class "Default")
      (node (ref "U$3") (pin "12") (pinfunction "VCC3_12") (pintype "bidirectional"))
    )
    (net (code "267") (name "unconnected-(U$3-VCC4-Pad14)") (class "Default")
      (node (ref "U$3") (pin "14") (pinfunction "VCC4_14") (pintype "bidirectional"))
    )
    (net (code "268") (name "unconnected-(U$3-VCC5-Pad16)") (class "Default")
      (node (ref "U$3") (pin "16") (pinfunction "VCC5_16") (pintype "bidirectional"))
    )
    (net (code "269") (name "unconnected-(U$3-VCC6-Pad18)") (class "Default")
      (node (ref "U$3") (pin "18") (pinfunction "VCC6_18") (pintype "bidirectional"))
    )
    (net (code "270") (name "unconnected-(U$3-VCC7-Pad70)") (class "Default")
      (node (ref "U$3") (pin "70") (pinfunction "VCC7_70") (pintype "bidirectional"))
    )
    (net (code "271") (name "unconnected-(U$3-VCC8-Pad72)") (class "Default")
      (node (ref "U$3") (pin "72") (pinfunction "VCC8_72") (pintype "bidirectional"))
    )
    (net (code "272") (name "unconnected-(U$3-VCC9-Pad74)") (class "Default")
      (node (ref "U$3") (pin "74") (pinfunction "VCC9_74") (pintype "bidirectional"))
    )
    (net (code "273") (name "unconnected-(U$3-~{CLKREQ}-Pad52)") (class "Default")
      (node (ref "U$3") (pin "52") (pinfunction "~{CLKREQ}_52") (pintype "bidirectional"))
    )
    (net (code "274") (name "unconnected-(U$3-~{PERST}-Pad50)") (class "Default")
      (node (ref "U$3") (pin "50") (pinfunction "~{PERST}_50") (pintype "bidirectional"))
    )
    (net (code "275") (name "unconnected-(U$3-~{PEWAKE}-Pad54)") (class "Default")
      (node (ref "U$3") (pin "54") (pinfunction "~{PEWAKE}_54") (pintype "bidirectional"))
    )
  )
)
